# AD.net
KiCad netlist of a schematic drawn in Altium Designer
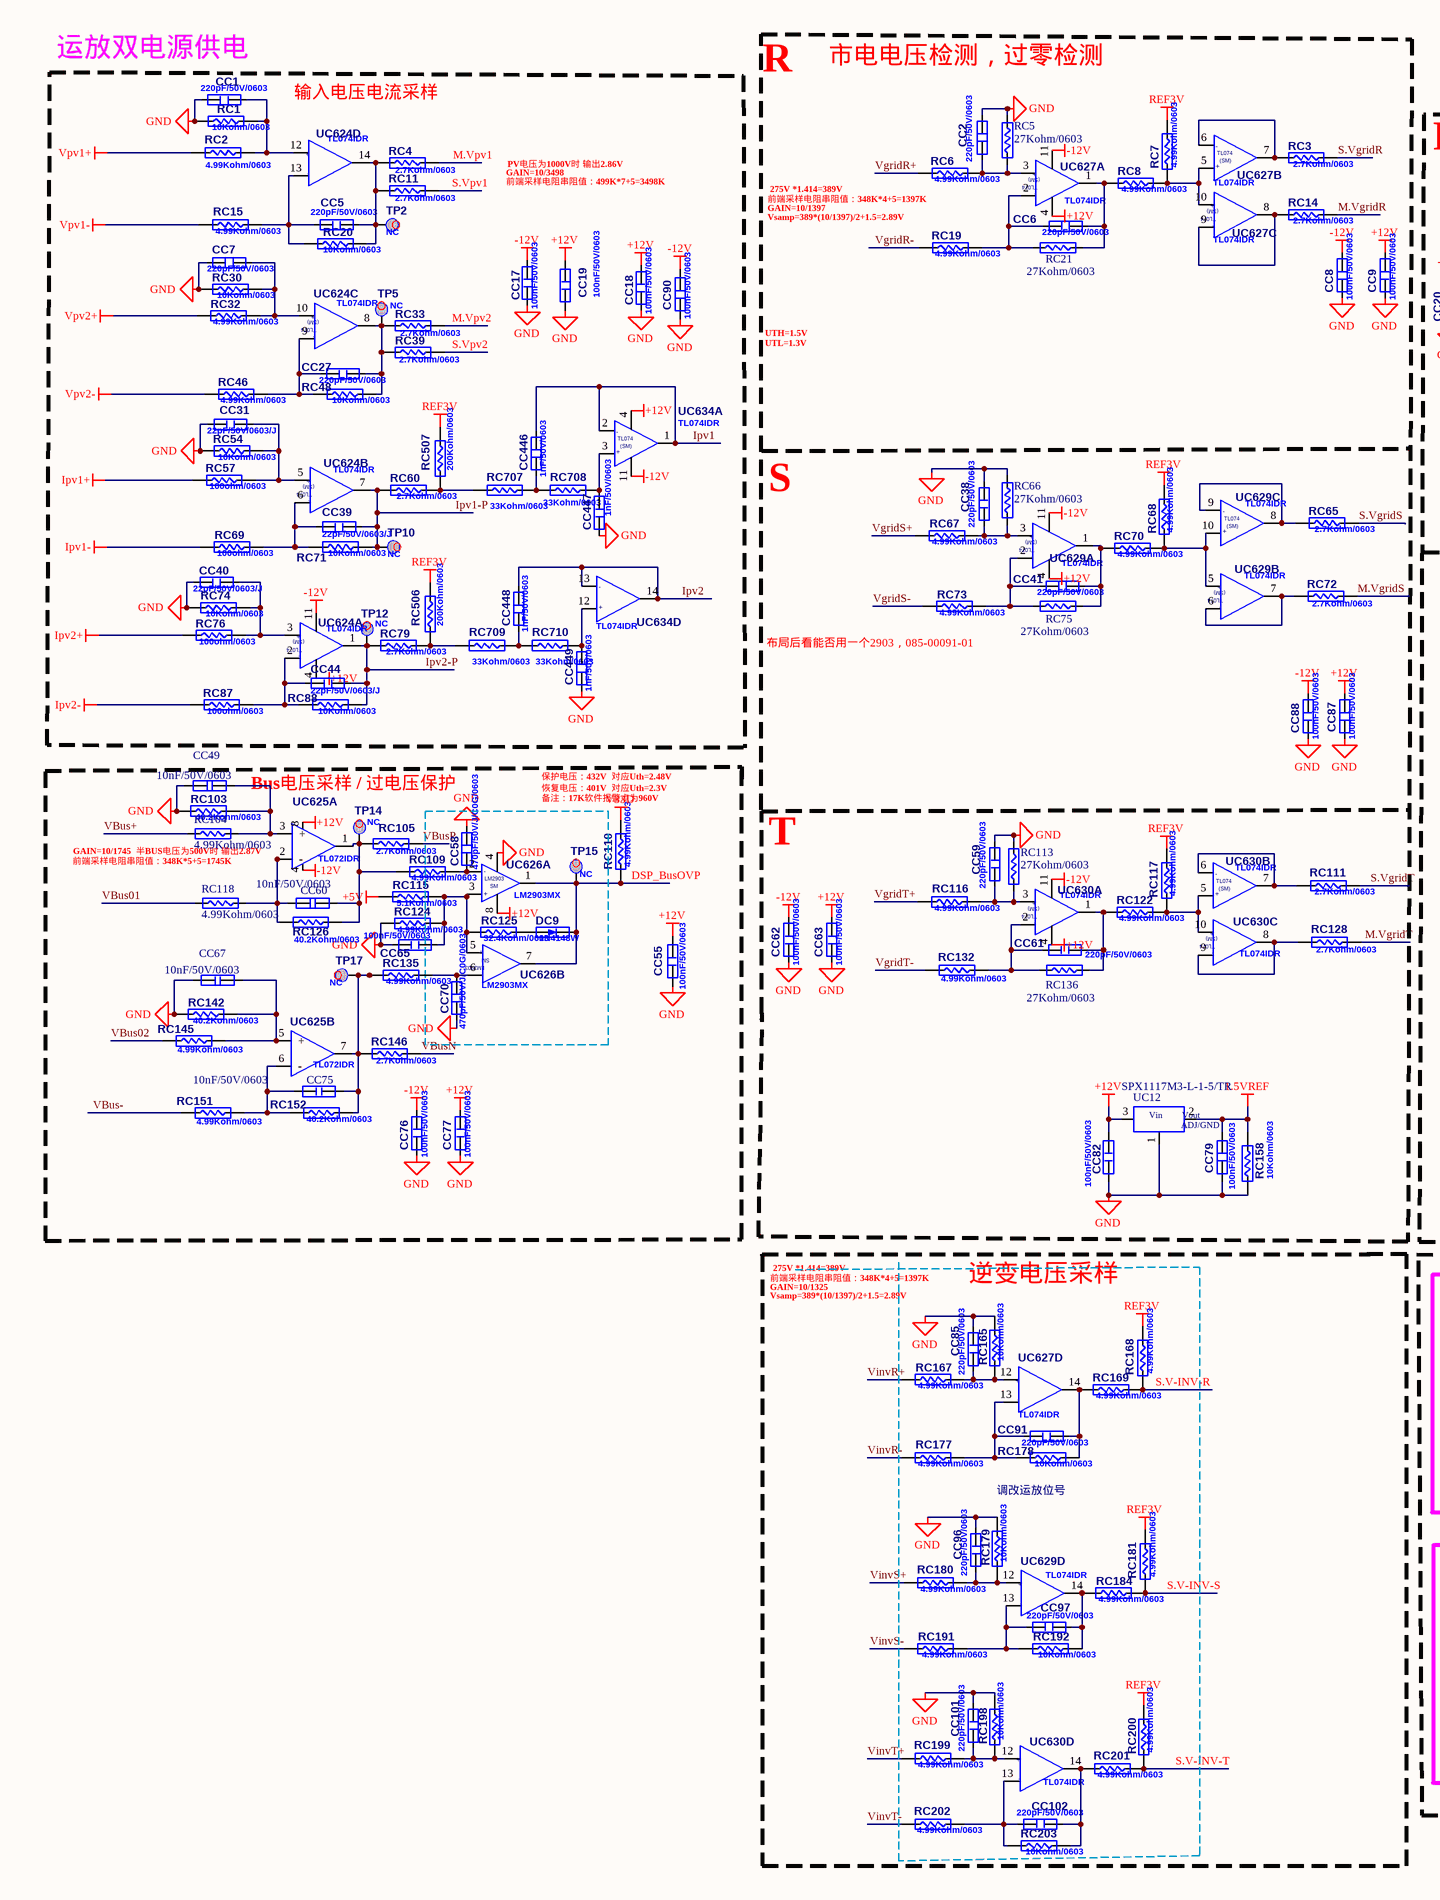
[diagram p0: AD.SchDoc, left]
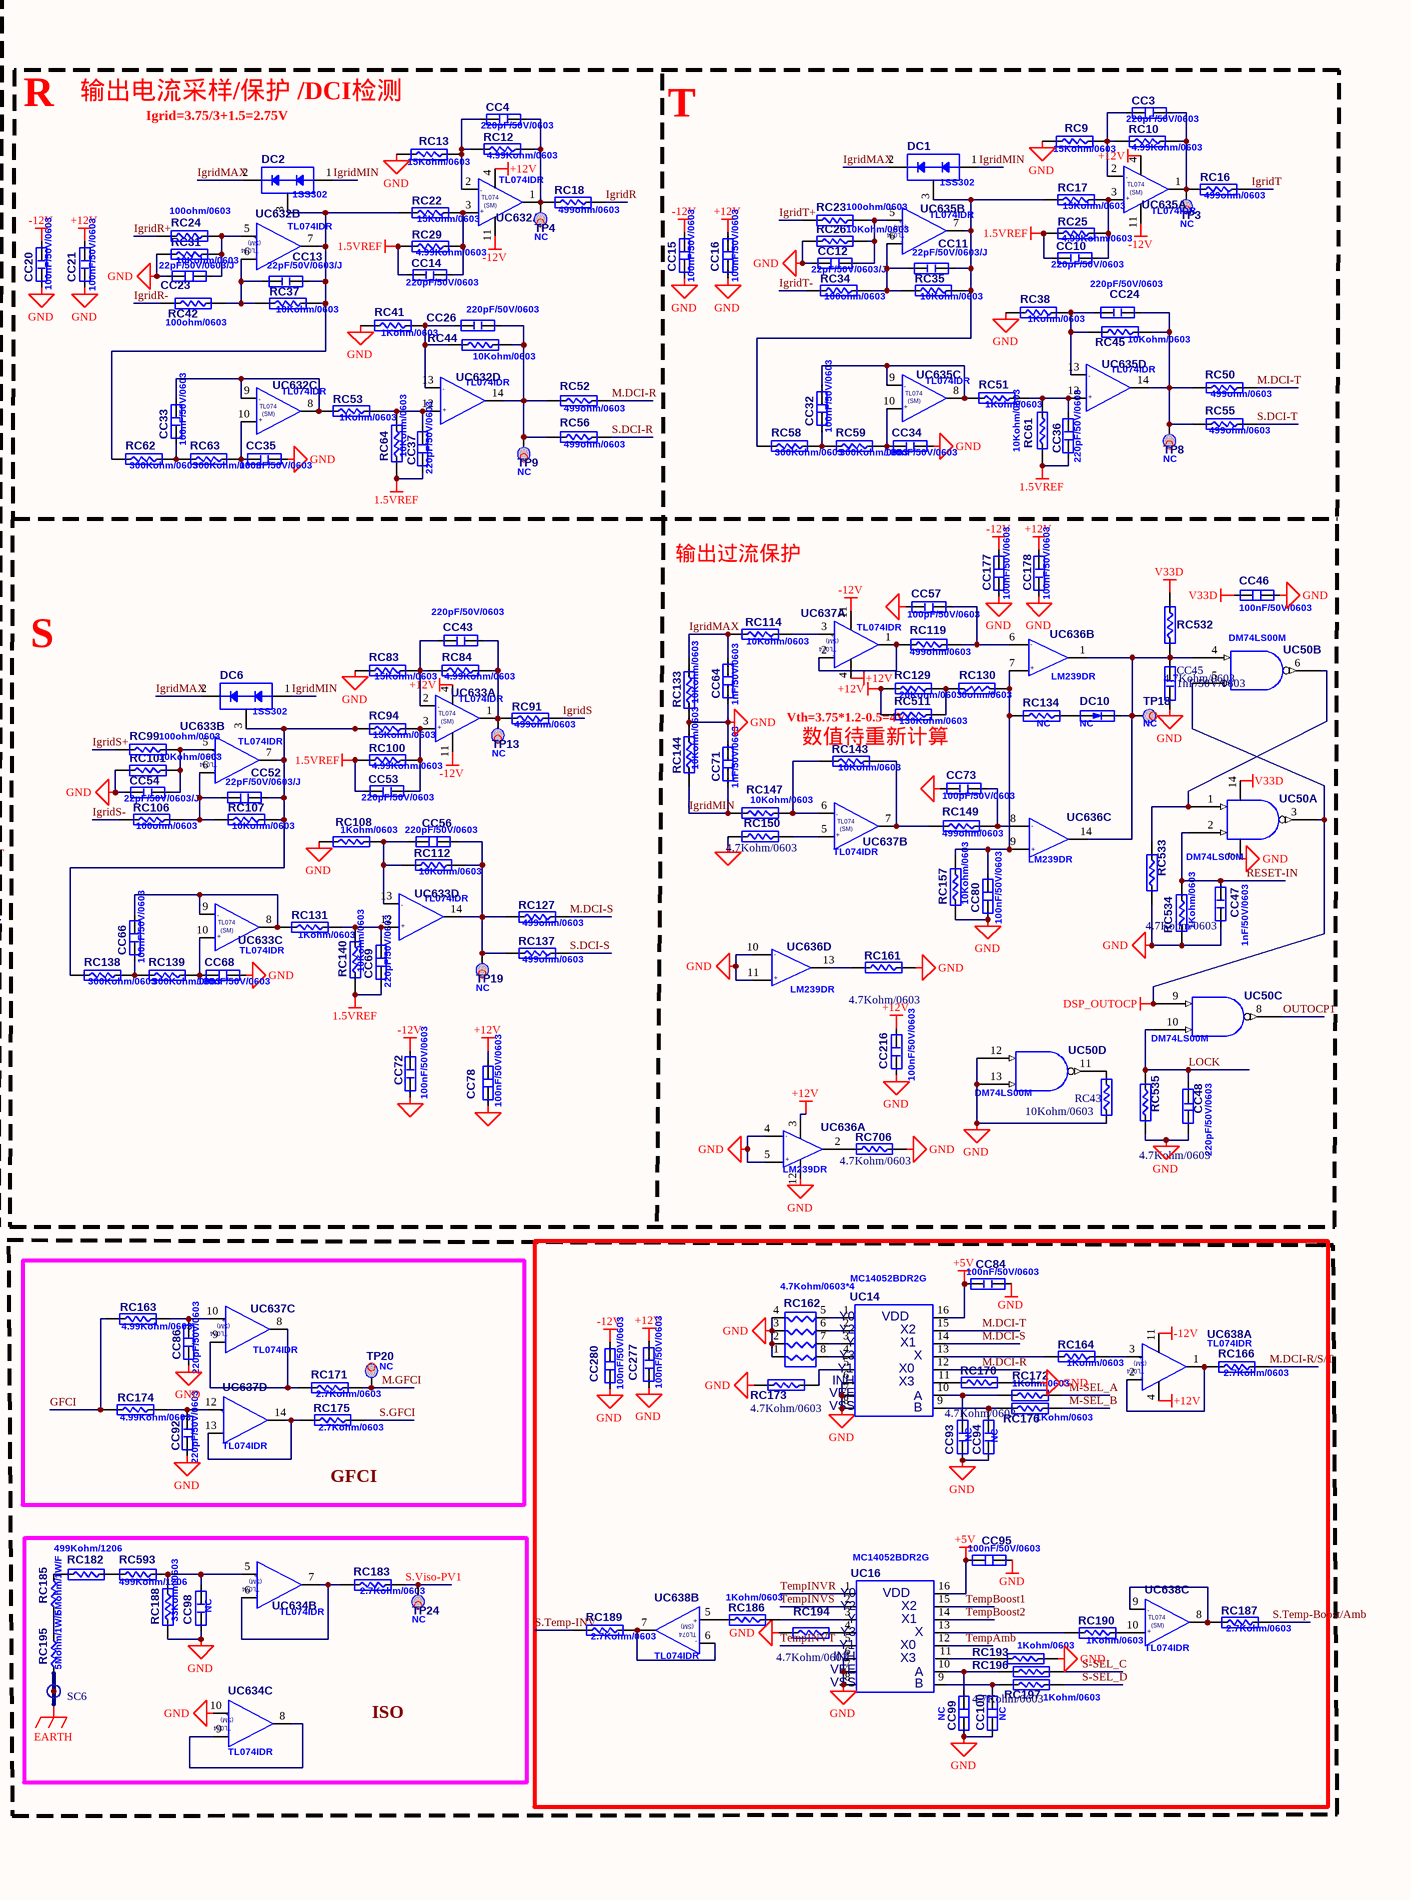
[diagram p1: AD.SchDoc, right]

(export (version "E")
  (design (tool "Eeschema 10.0.6"))
  (components
    (comp (ref "CC1")
      (value "220pF/50V/0603")
      (footprint "CC1608-0603")
      (description "220pF/50V/J/C0G/0603")
      (fields (field (name "Comment") "023-221220-0"))
      (libsource (lib "00") (part "C0603 SM"))
    )
    (comp (ref "CC2")
      (value "220pF/50V/0603")
      (footprint "CC1608-0603")
      (description "220pF/50V/J/C0G/0603")
      (fields (field (name "Comment") "023-221220-0"))
      (libsource (lib "00") (part "C0603 SM"))
    )
    (comp (ref "CC3")
      (value "220pF/50V/0603")
      (footprint "CC1608-0603")
      (description "220pF/50V/J/C0G/0603")
      (fields (field (name "Comment") "023-221220-0"))
      (libsource (lib "00") (part "C0603 SM"))
    )
    (comp (ref "CC4")
      (value "220pF/50V/0603")
      (footprint "CC1608-0603")
      (description "220pF/50V/J/C0G/0603")
      (fields (field (name "Comment") "023-221220-0"))
      (libsource (lib "00") (part "C0603 SM"))
    )
    (comp (ref "CC5")
      (value "220pF/50V/0603")
      (footprint "CC1608-0603")
      (description "220pF/50V/J/C0G/0603")
      (fields (field (name "Comment") "023-221220-0"))
      (libsource (lib "00") (part "C0603 SM"))
    )
    (comp (ref "CC6")
      (value "220pF/50V/0603")
      (footprint "CC1608-0603")
      (description "220pF/50V/J/C0G/0603")
      (fields (field (name "Comment") "023-221220-0"))
      (libsource (lib "00") (part "C0603 SM"))
    )
    (comp (ref "CC7")
      (value "220pF/50V/0603")
      (footprint "CC1608-0603")
      (description "220pF/50V/J/C0G/0603")
      (fields (field (name "Comment") "023-221220-0"))
      (libsource (lib "00") (part "C0603 SM"))
    )
    (comp (ref "CC8")
      (value "100nF/50V/0603")
      (footprint "CC1608-0603")
      (description "100nF/50V/J/X7R/0603")
      (fields (field (name "Comment") "023-105220-0"))
      (libsource (lib "00") (part "C0603 SM"))
    )
    (comp (ref "CC9")
      (value "100nF/50V/0603")
      (footprint "CC1608-0603")
      (description "100nF/50V/J/X7R/0603")
      (fields (field (name "Comment") "023-105220-0"))
      (libsource (lib "00") (part "C0603 SM"))
    )
    (comp (ref "CC10")
      (value "220pF/50V/0603")
      (footprint "CC1608-0603")
      (description "220pF/50V/J/C0G/0603")
      (fields (field (name "Comment") "023-221220-0"))
      (libsource (lib "00") (part "C0603 SM"))
    )
    (comp (ref "CC11")
      (value "22pF/50V/0603/J")
      (footprint "CC1608-0603")
      (description "22pF/50V/J/C0G/0603")
      (fields (field (name "Comment") "023-220220-0"))
      (libsource (lib "00") (part "C0603 SM"))
    )
    (comp (ref "CC12")
      (value "22pF/50V/0603/J")
      (footprint "CC1608-0603")
      (description "22pF/50V/J/C0G/0603")
      (fields (field (name "Comment") "023-220220-0"))
      (libsource (lib "00") (part "C0603 SM"))
    )
    (comp (ref "CC13")
      (value "22pF/50V/0603/J")
      (footprint "CC1608-0603")
      (description "22pF/50V/J/C0G/0603")
      (fields (field (name "Comment") "023-220220-0"))
      (libsource (lib "00") (part "C0603 SM"))
    )
    (comp (ref "CC14")
      (value "220pF/50V/0603")
      (footprint "CC1608-0603")
      (description "220pF/50V/J/C0G/0603")
      (fields (field (name "Comment") "023-221220-0"))
      (libsource (lib "00") (part "C0603 SM"))
    )
    (comp (ref "CC15")
      (value "100nF/50V/0603")
      (footprint "CC1608-0603")
      (description "100nF/50V/J/X7R/0603")
      (fields (field (name "Comment") "023-105220-0"))
      (libsource (lib "00") (part "C0603 SM"))
    )
    (comp (ref "CC16")
      (value "100nF/50V/0603")
      (footprint "CC1608-0603")
      (description "100nF/50V/J/X7R/0603")
      (fields (field (name "Comment") "023-105220-0"))
      (libsource (lib "00") (part "C0603 SM"))
    )
    (comp (ref "CC17")
      (value "100nF/50V/0603")
      (footprint "CC1608-0603")
      (description "100nF/50V/J/X7R/0603")
      (fields (field (name "Comment") "023-105220-0"))
      (libsource (lib "00") (part "C0603 SM"))
    )
    (comp (ref "CC18")
      (value "100nF/50V/0603")
      (footprint "CC1608-0603")
      (description "100nF/50V/J/X7R/0603")
      (fields (field (name "Comment") "023-105220-0"))
      (libsource (lib "00") (part "C0603 SM"))
    )
    (comp (ref "CC19")
      (value "100nF/50V/0603")
      (footprint "CC1608-0603")
      (description "100nF/50V/J/X7R/0603")
      (fields (field (name "Comment") "023-105220-0"))
      (libsource (lib "") (part "C0603 SM_1"))
    )
    (comp (ref "CC20")
      (value "100nF/50V/0603")
      (footprint "CC1608-0603")
      (description "100nF/50V/J/X7R/0603")
      (fields (field (name "Comment") "023-105220-0"))
      (libsource (lib "00") (part "C0603 SM"))
    )
    (comp (ref "CC21")
      (value "100nF/50V/0603")
      (footprint "CC1608-0603")
      (description "100nF/50V/J/X7R/0603")
      (fields (field (name "Comment") "023-105220-0"))
      (libsource (lib "00") (part "C0603 SM"))
    )
    (comp (ref "CC23")
      (value "22pF/50V/0603/J")
      (footprint "CC1608-0603")
      (description "22pF/50V/J/C0G/0603")
      (fields (field (name "Comment") "023-220220-0"))
      (libsource (lib "00") (part "C0603 SM"))
    )
    (comp (ref "CC24")
      (value "220pF/50V/0603")
      (footprint "CC1608-0603")
      (description "220pF/50V/J/C0G/0603")
      (fields (field (name "Comment") "023-221220-0"))
      (libsource (lib "00") (part "C0603 SM"))
    )
    (comp (ref "CC26")
      (value "220pF/50V/0603")
      (footprint "CC1608-0603")
      (description "220pF/50V/J/C0G/0603")
      (fields (field (name "Comment") "023-221220-0"))
      (libsource (lib "00") (part "C0603 SM"))
    )
    (comp (ref "CC27")
      (value "220pF/50V/0603")
      (footprint "CC1608-0603")
      (description "220pF/50V/J/C0G/0603")
      (fields (field (name "Comment") "023-221220-0"))
      (libsource (lib "00") (part "C0603 SM"))
    )
    (comp (ref "CC31")
      (value "22pF/50V/0603/J")
      (footprint "CC1608-0603")
      (description "22pF/50V/J/C0G/0603")
      (fields (field (name "Comment") "023-220220-0"))
      (libsource (lib "00") (part "C0603 SM"))
    )
    (comp (ref "CC32")
      (value "100nF/50V/0603")
      (footprint "CC1608-0603")
      (description "100nF/50V/J/X7R/0603")
      (fields (field (name "Comment") "023-105220-0"))
      (libsource (lib "00") (part "C0603 SM"))
    )
    (comp (ref "CC33")
      (value "100nF/50V/0603")
      (footprint "CC1608-0603")
      (description "100nF/50V/J/X7R/0603")
      (fields (field (name "Comment") "023-105220-0"))
      (libsource (lib "00") (part "C0603 SM"))
    )
    (comp (ref "CC34")
      (value "100nF/50V/0603")
      (footprint "CC1608-0603")
      (description "100nF/50V/J/X7R/0603")
      (fields (field (name "Comment") "023-105220-0"))
      (libsource (lib "00") (part "C0603 SM"))
    )
    (comp (ref "CC35")
      (value "100nF/50V/0603")
      (footprint "CC1608-0603")
      (description "100nF/50V/J/X7R/0603")
      (fields (field (name "Comment") "023-105220-0"))
      (libsource (lib "00") (part "C0603 SM"))
    )
    (comp (ref "CC36")
      (value "220pF/50V/0603")
      (footprint "CC1608-0603")
      (description "220pF/50V/J/C0G/0603")
      (fields (field (name "Comment") "023-221220-0"))
      (libsource (lib "00") (part "C0603 SM"))
    )
    (comp (ref "CC37")
      (value "220pF/50V/0603")
      (footprint "CC1608-0603")
      (description "220pF/50V/J/C0G/0603")
      (fields (field (name "Comment") "023-221220-0"))
      (libsource (lib "00") (part "C0603 SM"))
    )
    (comp (ref "CC38")
      (value "220pF/50V/0603")
      (footprint "CC1608-0603")
      (description "220pF/50V/J/C0G/0603")
      (fields (field (name "Comment") "023-221220-0"))
      (libsource (lib "00") (part "C0603 SM"))
    )
    (comp (ref "CC39")
      (value "22pF/50V/0603/J")
      (footprint "CC1608-0603")
      (description "22pF/50V/J/C0G/0603")
      (fields (field (name "Comment") "023-220220-0"))
      (libsource (lib "00") (part "C0603 SM"))
    )
    (comp (ref "CC40")
      (value "22pF/50V/0603/J")
      (footprint "CC1608-0603")
      (description "22pF/50V/J/C0G/0603")
      (fields (field (name "Comment") "023-220220-0"))
      (libsource (lib "00") (part "C0603 SM"))
    )
    (comp (ref "CC41")
      (value "220pF/50V/0603")
      (footprint "CC1608-0603")
      (description "220pF/50V/J/C0G/0603")
      (fields (field (name "Comment") "023-221220-0"))
      (libsource (lib "00") (part "C0603 SM"))
    )
    (comp (ref "CC43")
      (value "220pF/50V/0603")
      (footprint "CC1608-0603")
      (description "220pF/50V/J/C0G/0603")
      (fields (field (name "Comment") "023-221220-0"))
      (libsource (lib "00") (part "C0603 SM"))
    )
    (comp (ref "CC44")
      (value "22pF/50V/0603/J")
      (footprint "CC1608-0603")
      (description "22pF/50V/J/C0G/0603")
      (fields (field (name "Comment") "023-220220-0"))
      (libsource (lib "00") (part "C0603 SM"))
    )
    (comp (ref "CC45")
      (value "1nF/50V/0603")
      (footprint "C0603SM")
      (description "1nF/50V/J/C0G/0603")
      (fields (field (name "Comment") "023-102220-0"))
      (libsource (lib "首航") (part "023-102220-0 C0603SM"))
    )
    (comp (ref "CC46")
      (value "100nF/50V/0603")
      (footprint "CC1608-0603")
      (description "100nF/50V/J/X7R/0603")
      (fields (field (name "Comment") "023-105220-0"))
      (libsource (lib "CAP") (part "CC0603-104SM"))
    )
    (comp (ref "CC47")
      (value "1nF/50V/0603")
      (footprint "CC1608-0603")
      (description "1nF/50V/J/C0G/0603")
      (fields (field (name "Comment") "023-102220-0"))
      (libsource (lib "*") (part "C0603 SM"))
    )
    (comp (ref "CC48")
      (value "220pF/50V/0603")
      (footprint "CC1608-0603")
      (description "220pF/50V/J/C0G/0603")
      (fields (field (name "Comment") "023-221220-0"))
      (libsource (lib "*") (part "C0603SM-3"))
    )
    (comp (ref "CC49")
      (value "10nF/50V/0603")
      (footprint "C0603SM")
      (description "10nF/50V/J/X7R/0603")
      (fields (field (name "Comment") "023-103220-0"))
      (libsource (lib "首航") (part "023-103220-0 C0603SM"))
    )
    (comp (ref "CC52")
      (value "22pF/50V/0603/J")
      (footprint "CC1608-0603")
      (description "22pF/50V/J/C0G/0603")
      (fields (field (name "Comment") "023-220220-0"))
      (libsource (lib "00") (part "C0603 SM"))
    )
    (comp (ref "CC53")
      (value "220pF/50V/0603")
      (footprint "CC1608-0603")
      (description "220pF/50V/J/C0G/0603")
      (fields (field (name "Comment") "023-221220-0"))
      (libsource (lib "00") (part "C0603 SM"))
    )
    (comp (ref "CC54")
      (value "22pF/50V/0603/J")
      (footprint "CC1608-0603")
      (description "22pF/50V/J/C0G/0603")
      (fields (field (name "Comment") "023-220220-0"))
      (libsource (lib "00") (part "C0603 SM"))
    )
    (comp (ref "CC55")
      (value "100nF/50V/0603")
      (footprint "CC1608-0603")
      (description "100nF/50V/J/X7R/0603")
      (fields (field (name "Comment") "023-105220-0"))
      (libsource (lib "") (part "C0603 SM_1"))
    )
    (comp (ref "CC56")
      (value "220pF/50V/0603")
      (footprint "CC1608-0603")
      (description "220pF/50V/J/C0G/0603")
      (fields (field (name "Comment") "023-221220-0"))
      (libsource (lib "") (part "C0603 SM_1"))
    )
    (comp (ref "CC57")
      (value "100pF/50V/0603")
      (footprint "CC1608-0603")
      (description "100pF/50V/J/C0G/0603")
      (fields (field (name "Comment") "023-101220-0"))
      (libsource (lib "*") (part "C0603 SM"))
    )
    (comp (ref "CC58")
      (value "470pF/50V/J/C0G/0603")
      (footprint "CC1608-0603")
      (fields (field (name "Comment") "023-471220-0"))
      (libsource (lib "00") (part "C0603 SM"))
    )
    (comp (ref "CC59")
      (value "220pF/50V/0603")
      (footprint "CC1608-0603")
      (description "220pF/50V/J/C0G/0603")
      (fields (field (name "Comment") "023-221220-0"))
      (libsource (lib "00") (part "C0603 SM"))
    )
    (comp (ref "CC60")
      (value "10nF/50V/0603")
      (footprint "C0603SM")
      (description "10nF/50V/J/X7R/0603")
      (fields (field (name "Comment") "023-103220-0"))
      (libsource (lib "首航") (part "023-103220-0 C0603SM"))
    )
    (comp (ref "CC61")
      (value "220pF/50V/0603")
      (footprint "CC1608-0603")
      (description "220pF/50V/J/C0G/0603")
      (fields (field (name "Comment") "023-221220-0"))
      (libsource (lib "00") (part "C0603 SM"))
    )
    (comp (ref "CC62")
      (value "100nF/50V/0603")
      (footprint "CC1608-0603")
      (description "100nF/50V/J/X7R/0603")
      (fields (field (name "Comment") "023-105220-0"))
      (libsource (lib "00") (part "C0603 SM"))
    )
    (comp (ref "CC63")
      (value "100nF/50V/0603")
      (footprint "CC1608-0603")
      (description "100nF/50V/J/X7R/0603")
      (fields (field (name "Comment") "023-105220-0"))
      (libsource (lib "00") (part "C0603 SM"))
    )
    (comp (ref "CC64")
      (value "1nF/50V/0603")
      (footprint "CC1608-0603")
      (description "1nF/50V/J/C0G/0603")
      (fields (field (name "Comment") "023-102220-0"))
      (libsource (lib "*") (part "C0603 SM"))
    )
    (comp (ref "CC65")
      (value "100nF/50V/0603")
      (footprint "CC1608-0603")
      (description "100nF/50V/J/X7R/0603")
      (fields (field (name "Comment") "023-105220-0"))
      (libsource (lib "00") (part "C0603 SM"))
    )
    (comp (ref "CC66")
      (value "100nF/50V/0603")
      (footprint "CC1608-0603")
      (description "100nF/50V/J/X7R/0603")
      (fields (field (name "Comment") "023-105220-0"))
      (libsource (lib "00") (part "C0603 SM"))
    )
    (comp (ref "CC67")
      (value "10nF/50V/0603")
      (footprint "C0603SM")
      (description "10nF/50V/J/X7R/0603")
      (fields (field (name "Comment") "023-103220-0"))
      (libsource (lib "首航") (part "023-103220-0 C0603SM"))
    )
    (comp (ref "CC68")
      (value "100nF/50V/0603")
      (footprint "CC1608-0603")
      (description "100nF/50V/J/X7R/0603")
      (fields (field (name "Comment") "023-105220-0"))
      (libsource (lib "00") (part "C0603 SM"))
    )
    (comp (ref "CC69")
      (value "220pF/50V/0603")
      (footprint "CC1608-0603")
      (description "220pF/50V/J/C0G/0603")
      (fields (field (name "Comment") "023-221220-0"))
      (libsource (lib "") (part "C0603 SM_1"))
    )
    (comp (ref "CC70")
      (value "470pF/50V/J/C0G/0603")
      (footprint "CC1608-0603")
      (fields (field (name "Comment") "023-471220-0"))
      (libsource (lib "00") (part "C0603 SM"))
    )
    (comp (ref "CC71")
      (value "1nF/50V/0603")
      (footprint "CC1608-0603")
      (description "1nF/50V/J/C0G/0603")
      (fields (field (name "Comment") "023-102220-0"))
      (libsource (lib "*") (part "C0603 SM"))
    )
    (comp (ref "CC72")
      (value "100nF/50V/0603")
      (footprint "CC1608-0603")
      (description "100nF/50V/J/X7R/0603")
      (fields (field (name "Comment") "023-105220-0"))
      (libsource (lib "*") (part "C0603 SM"))
    )
    (comp (ref "CC73")
      (value "100pF/50V/0603")
      (footprint "CC1608-0603")
      (description "100pF/50V/J/C0G/0603")
      (fields (field (name "Comment") "023-101220-0"))
      (libsource (lib "*") (part "C0603 SM"))
    )
    (comp (ref "CC75")
      (value "10nF/50V/0603")
      (footprint "C0603SM")
      (description "10nF/50V/J/X7R/0603")
      (fields (field (name "Comment") "023-103220-0"))
      (libsource (lib "首航") (part "023-103220-0 C0603SM"))
    )
    (comp (ref "CC76")
      (value "100nF/50V/0603")
      (footprint "CC1608-0603")
      (description "100nF/50V/J/X7R/0603")
      (fields (field (name "Comment") "023-105220-0"))
      (libsource (lib "00") (part "C0603 SM"))
    )
    (comp (ref "CC77")
      (value "100nF/50V/0603")
      (footprint "CC1608-0603")
      (description "100nF/50V/J/X7R/0603")
      (fields (field (name "Comment") "023-105220-0"))
      (libsource (lib "00") (part "C0603 SM"))
    )
    (comp (ref "CC78")
      (value "100nF/50V/0603")
      (footprint "CC1608-0603")
      (description "100nF/50V/J/X7R/0603")
      (fields (field (name "Comment") "023-105220-0"))
      (libsource (lib "*") (part "C0603 SM"))
    )
    (comp (ref "CC79")
      (value "100nF/50V/0603")
      (footprint "CC1608-0603")
      (description "100nF/50V/J/X7R/0603")
      (fields (field (name "Comment") "023-105220-0"))
      (libsource (lib "") (part "C0603 SM_1"))
    )
    (comp (ref "CC80")
      (value "100nF/50V/0603")
      (footprint "CC1608-0603")
      (description "100nF/50V/J/X7R/0603")
      (fields (field (name "Comment") "023-105220-0"))
      (libsource (lib "00") (part "C0603 SM"))
    )
    (comp (ref "CC82")
      (value "100nF/50V/0603")
      (footprint "CC1608-0603")
      (description "100nF/50V/J/X7R/0603")
      (fields (field (name "Comment") "023-105220-0"))
      (libsource (lib "") (part "C0603 SM_1"))
    )
    (comp (ref "CC84")
      (value "100nF/50V/0603")
      (footprint "CC1608-0603")
      (description "100nF/50V/J/X7R/0603")
      (fields (field (name "Comment") "023-105220-0"))
      (libsource (lib "00") (part "C0603 SM"))
    )
    (comp (ref "CC85")
      (value "220pF/50V/0603")
      (footprint "CC1608-0603")
      (description "220pF/50V/J/C0G/0603")
      (fields (field (name "Comment") "023-221220-0"))
      (libsource (lib "00") (part "C0603 SM"))
    )
    (comp (ref "CC86")
      (value "220pF/50V/0603")
      (footprint "CC1608-0603")
      (description "220pF/50V/J/C0G/0603")
      (fields (field (name "Comment") "023-221220-0"))
      (libsource (lib "00") (part "C0603 SM"))
    )
    (comp (ref "CC87")
      (value "100nF/50V/0603")
      (footprint "CC1608-0603")
      (description "100nF/50V/J/X7R/0603")
      (fields (field (name "Comment") "023-105220-0"))
      (libsource (lib "00") (part "C0603 SM"))
    )
    (comp (ref "CC88")
      (value "100nF/50V/0603")
      (footprint "CC1608-0603")
      (description "100nF/50V/J/X7R/0603")
      (fields (field (name "Comment") "023-105220-0"))
      (libsource (lib "00") (part "C0603 SM"))
    )
    (comp (ref "CC90")
      (value "100nF/50V/0603")
      (footprint "CC1608-0603")
      (description "100nF/50V/J/X7R/0603")
      (fields (field (name "Comment") "023-105220-0"))
      (libsource (lib "") (part "C0603 SM_1"))
    )
    (comp (ref "CC91")
      (value "220pF/50V/0603")
      (footprint "CC1608-0603")
      (description "220pF/50V/J/C0G/0603")
      (fields (field (name "Comment") "023-221220-0"))
      (libsource (lib "00") (part "C0603 SM"))
    )
    (comp (ref "CC92")
      (value "220pF/50V/0603")
      (footprint "CC1608-0603")
      (description "220pF/50V/J/C0G/0603")
      (fields (field (name "Comment") "023-221220-0"))
      (libsource (lib "00") (part "C0603 SM"))
    )
    (comp (ref "CC93") (value "NC") (footprint "CC1608-0603") (libsource (lib "00") (part "C0603 SM")))
    (comp (ref "CC94") (value "NC") (footprint "CC1608-0603") (libsource (lib "00") (part "C0603 SM")))
    (comp (ref "CC95")
      (value "100nF/50V/0603")
      (footprint "CC1608-0603")
      (description "100nF/50V/J/X7R/0603")
      (fields (field (name "Comment") "023-105220-0"))
      (libsource (lib "00") (part "C0603 SM"))
    )
    (comp (ref "CC96")
      (value "220pF/50V/0603")
      (footprint "CC1608-0603")
      (description "220pF/50V/J/C0G/0603")
      (fields (field (name "Comment") "023-221220-0"))
      (libsource (lib "00") (part "C0603 SM"))
    )
    (comp (ref "CC97")
      (value "220pF/50V/0603")
      (footprint "CC1608-0603")
      (description "220pF/50V/J/C0G/0603")
      (fields (field (name "Comment") "023-221220-0"))
      (libsource (lib "00") (part "C0603 SM"))
    )
    (comp (ref "CC98") (value "NC") (footprint "CC1608-0603") (libsource (lib "00") (part "C0603 SM")))
    (comp (ref "CC99") (value "NC") (footprint "CC1608-0603") (libsource (lib "00") (part "C0603 SM")))
    (comp (ref "CC100") (value "NC") (footprint "CC1608-0603") (libsource (lib "00") (part "C0603 SM")))
    (comp (ref "CC101")
      (value "220pF/50V/0603")
      (footprint "CC1608-0603")
      (description "220pF/50V/J/C0G/0603")
      (fields (field (name "Comment") "023-221220-0"))
      (libsource (lib "00") (part "C0603 SM"))
    )
    (comp (ref "CC102")
      (value "220pF/50V/0603")
      (footprint "CC1608-0603")
      (description "220pF/50V/J/C0G/0603")
      (fields (field (name "Comment") "023-221220-0"))
      (libsource (lib "00") (part "C0603 SM"))
    )
    (comp (ref "CC177")
      (value "100nF/50V/0603")
      (footprint "CC1608-0603")
      (description "100nF/50V/J/X7R/0603")
      (fields (field (name "Comment") "023-105220-0"))
      (libsource (lib "00") (part "C0603 SM"))
    )
    (comp (ref "CC178")
      (value "100nF/50V/0603")
      (footprint "CC1608-0603")
      (description "100nF/50V/J/X7R/0603")
      (fields (field (name "Comment") "023-105220-0"))
      (libsource (lib "00") (part "C0603 SM"))
    )
    (comp (ref "CC216")
      (value "100nF/50V/0603")
      (footprint "CC1608-0603")
      (description "100nF/50V/J/X7R/0603")
      (fields (field (name "Comment") "023-105220-0"))
      (libsource (lib "00") (part "C0603 SM"))
    )
    (comp (ref "CC277")
      (value "100nF/50V/0603")
      (footprint "CC1608-0603")
      (description "100nF/50V/J/X7R/0603")
      (fields (field (name "Comment") "023-105220-0"))
      (libsource (lib "00") (part "C0603 SM"))
    )
    (comp (ref "CC280")
      (value "100nF/50V/0603")
      (footprint "CC1608-0603")
      (description "100nF/50V/J/X7R/0603")
      (fields (field (name "Comment") "023-105220-0"))
      (libsource (lib "00") (part "C0603 SM"))
    )
    (comp (ref "CC446")
      (value "1nF/50V/0603")
      (footprint "CC1608-0603")
      (description "1nF/50V/J/C0G/0603")
      (fields (field (name "Comment") "023-102220-0"))
      (libsource (lib "00") (part "C0603 SM"))
    )
    (comp (ref "CC447")
      (value "1nF/50V/0603")
      (footprint "CC1608-0603")
      (description "1nF/50V/J/C0G/0603")
      (fields (field (name "Comment") "023-102220-0"))
      (libsource (lib "00") (part "C0603 SM"))
    )
    (comp (ref "CC448")
      (value "1nF/50V/0603")
      (footprint "CC1608-0603")
      (description "1nF/50V/J/C0G/0603")
      (fields (field (name "Comment") "023-102220-0"))
      (libsource (lib "00") (part "C0603 SM"))
    )
    (comp (ref "CC449")
      (value "1nF/50V/0603")
      (footprint "CC1608-0603")
      (description "1nF/50V/J/C0G/0603")
      (fields (field (name "Comment") "023-102220-0"))
      (libsource (lib "00") (part "C0603 SM"))
    )
    (comp (ref "DC1")
      (value "1SS302")
      (footprint "SC-70")
      (description "0.1A/80V/SC-70")
      (fields (field (name "Comment") "060-610010-0"))
      (libsource (lib "00") (part "17K1SS302"))
    )
    (comp (ref "DC2")
      (value "1SS302")
      (footprint "SC-70")
      (description "0.1A/80V/SC-70")
      (fields (field (name "Comment") "060-610010-0"))
      (libsource (lib "00") (part "17K1SS302"))
    )
    (comp (ref "DC6")
      (value "1SS302")
      (footprint "SC-70")
      (description "0.1A/80V/SC-70")
      (fields (field (name "Comment") "060-610010-0"))
      (libsource (lib "00") (part "17K1SS302"))
    )
    (comp (ref "DC9")
      (value "1N4148W")
      (footprint "SOD-123")
      (description "0.15A/75V/SOD-123")
      (fields (field (name "Comment") "060-500010-0"))
      (libsource (lib "00") (part "D 1N4148W"))
    )
    (comp (ref "DC10") (value "NC") (footprint "SOD-123") (libsource (lib "00") (part "D 1N4148W")))
    (comp (ref "RC1")
      (value "10Kohm/0603")
      (footprint "R1608-0603")
      (description "10Kohm/1/10W/F/0603")
      (fields (field (name "Comment") "011-103020-0"))
      (libsource (lib "00") (part "R0603SM"))
    )
    (comp (ref "RC2")
      (value "4.99Kohm/0603")
      (footprint "R1608-0603")
      (description "4.99Kohm/1/10W/F/0603")
      (fields (field (name "Comment") "011-492020-0"))
      (libsource (lib "00") (part "R0603SM"))
    )
    (comp (ref "RC3")
      (value "2.7Kohm/0603")
      (footprint "R1608-0603")
      (description "2.7Kohm/1/10W/F/0603")
      (fields (field (name "Comment") "011-272020-0"))
      (libsource (lib "00") (part "R0603SM"))
    )
    (comp (ref "RC4")
      (value "2.7Kohm/0603")
      (footprint "R1608-0603")
      (description "2.7Kohm/1/10W/F/0603")
      (fields (field (name "Comment") "011-272020-0"))
      (libsource (lib "00") (part "R0603SM"))
    )
    (comp (ref "RC5")
      (value "27Kohm/0603")
      (footprint "R0603SM")
      (description "27Kohm/1/10W/F/0603")
      (fields (field (name "Comment") "011-273020-0"))
      (libsource (lib "首航") (part "011-273020-0 R0603SM"))
    )
    (comp (ref "RC6")
      (value "4.99Kohm/0603")
      (footprint "R1608-0603")
      (description "4.99Kohm/1/10W/F/0603")
      (fields (field (name "Comment") "011-492020-0"))
      (libsource (lib "00") (part "R0603SM"))
    )
    (comp (ref "RC7")
      (value "4.99Kohm/0603")
      (footprint "R1608-0603")
      (description "4.99Kohm/1/10W/F/0603")
      (fields (field (name "Comment") "011-492020-0"))
      (libsource (lib "00") (part "R0603SM"))
    )
    (comp (ref "RC8")
      (value "4.99Kohm/0603")
      (footprint "R1608-0603")
      (description "4.99Kohm/1/10W/F/0603")
      (fields (field (name "Comment") "011-492020-0"))
      (libsource (lib "00") (part "R0603SM"))
    )
    (comp (ref "RC9")
      (value "15Kohm/0603")
      (footprint "R1608-0603")
      (description "15Kohm/1/10W/F/0603")
      (fields (field (name "Comment") "011-153020-0"))
      (libsource (lib "00") (part "R0603SM"))
    )
    (comp (ref "RC10")
      (value "4.99Kohm/0603")
      (footprint "R1608-0603")
      (description "4.99Kohm/1/10W/F/0603")
      (fields (field (name "Comment") "011-492020-0"))
      (libsource (lib "00") (part "R0603SM"))
    )
    (comp (ref "RC11")
      (value "2.7Kohm/0603")
      (footprint "R1608-0603")
      (description "2.7Kohm/1/10W/F/0603")
      (fields (field (name "Comment") "011-272020-0"))
      (libsource (lib "00") (part "R0603SM"))
    )
    (comp (ref "RC12")
      (value "4.99Kohm/0603")
      (footprint "R1608-0603")
      (description "4.99Kohm/1/10W/F/0603")
      (fields (field (name "Comment") "011-492020-0"))
      (libsource (lib "00") (part "R0603SM"))
    )
    (comp (ref "RC13")
      (value "15Kohm/0603")
      (footprint "R1608-0603")
      (description "15Kohm/1/10W/F/0603")
      (fields (field (name "Comment") "011-153020-0"))
      (libsource (lib "00") (part "R0603SM"))
    )
    (comp (ref "RC14")
      (value "2.7Kohm/0603")
      (footprint "R1608-0603")
      (description "2.7Kohm/1/10W/F/0603")
      (fields (field (name "Comment") "011-272020-0"))
      (libsource (lib "00") (part "R0603SM"))
    )
    (comp (ref "RC15")
      (value "4.99Kohm/0603")
      (footprint "R1608-0603")
      (description "4.99Kohm/1/10W/F/0603")
      (fields (field (name "Comment") "011-492020-0"))
      (libsource (lib "00") (part "R0603SM"))
    )
    (comp (ref "RC16")
      (value "499ohm/0603")
      (footprint "R1608-0603")
      (description "499ohm/1/10W/F/0603")
      (fields (field (name "Comment") "011-491020-0"))
      (libsource (lib "00") (part "R0603SM"))
    )
    (comp (ref "RC17")
      (value "15Kohm/0603")
      (footprint "R1608-0603")
      (description "15Kohm/1/10W/F/0603")
      (fields (field (name "Comment") "011-153020-0"))
      (libsource (lib "00") (part "R0603SM"))
    )
    (comp (ref "RC18")
      (value "499ohm/0603")
      (footprint "R1608-0603")
      (description "499ohm/1/10W/F/0603")
      (fields (field (name "Comment") "011-491020-0"))
      (libsource (lib "00") (part "R0603SM"))
    )
    (comp (ref "RC19")
      (value "4.99Kohm/0603")
      (footprint "R1608-0603")
      (description "4.99Kohm/1/10W/F/0603")
      (fields (field (name "Comment") "011-492020-0"))
      (libsource (lib "00") (part "R0603SM"))
    )
    (comp (ref "RC20")
      (value "10Kohm/0603")
      (footprint "R1608-0603")
      (description "10Kohm/1/10W/F/0603")
      (fields (field (name "Comment") "011-103020-0"))
      (libsource (lib "00") (part "R0603SM"))
    )
    (comp (ref "RC21")
      (value "27Kohm/0603")
      (footprint "R0603SM")
      (description "27Kohm/1/10W/F/0603")
      (fields (field (name "Comment") "011-273020-0"))
      (libsource (lib "首航") (part "011-273020-0 R0603SM"))
    )
    (comp (ref "RC22")
      (value "15Kohm/0603")
      (footprint "R1608-0603")
      (description "15Kohm/1/10W/F/0603")
      (fields (field (name "Comment") "011-153020-0"))
      (libsource (lib "00") (part "R0603SM"))
    )
    (comp (ref "RC23")
      (value "100ohm/0603")
      (footprint "R1608-0603")
      (description "100ohm/1/10W/F/0603")
      (fields (field (name "Comment") "011-101020-0"))
      (libsource (lib "00") (part "R0603SM"))
    )
    (comp (ref "RC24")
      (value "100ohm/0603")
      (footprint "R1608-0603")
      (description "100ohm/1/10W/F/0603")
      (fields (field (name "Comment") "011-101020-0"))
      (libsource (lib "00") (part "R0603SM"))
    )
    (comp (ref "RC25")
      (value "4.99Kohm/0603")
      (footprint "R1608-0603")
      (description "4.99Kohm/1/10W/F/0603")
      (fields (field (name "Comment") "011-492020-0"))
      (libsource (lib "00") (part "R0603SM"))
    )
    (comp (ref "RC26")
      (value "10Kohm/0603")
      (footprint "R1608-0603")
      (description "10Kohm/1/10W/F/0603")
      (fields (field (name "Comment") "011-103020-0"))
      (libsource (lib "00") (part "R0603SM"))
    )
    (comp (ref "RC29")
      (value "4.99Kohm/0603")
      (footprint "R1608-0603")
      (description "4.99Kohm/1/10W/F/0603")
      (fields (field (name "Comment") "011-492020-0"))
      (libsource (lib "00") (part "R0603SM"))
    )
    (comp (ref "RC30")
      (value "10Kohm/0603")
      (footprint "R1608-0603")
      (description "10Kohm/1/10W/F/0603")
      (fields (field (name "Comment") "011-103020-0"))
      (libsource (lib "00") (part "R0603SM"))
    )
    (comp (ref "RC31")
      (value "10Kohm/0603")
      (footprint "R1608-0603")
      (description "10Kohm/1/10W/F/0603")
      (fields (field (name "Comment") "011-103020-0"))
      (libsource (lib "00") (part "R0603SM"))
    )
    (comp (ref "RC32")
      (value "4.99Kohm/0603")
      (footprint "R1608-0603")
      (description "4.99Kohm/1/10W/F/0603")
      (fields (field (name "Comment") "011-492020-0"))
      (libsource (lib "00") (part "R0603SM"))
    )
    (comp (ref "RC33")
      (value "2.7Kohm/0603")
      (footprint "R1608-0603")
      (description "2.7Kohm/1/10W/F/0603")
      (fields (field (name "Comment") "011-272020-0"))
      (libsource (lib "00") (part "R0603SM"))
    )
    (comp (ref "RC34")
      (value "100ohm/0603")
      (footprint "R1608-0603")
      (description "100ohm/1/10W/F/0603")
      (fields (field (name "Comment") "011-101020-0"))
      (libsource (lib "00") (part "R0603SM"))
    )
    (comp (ref "RC35")
      (value "10Kohm/0603")
      (footprint "R1608-0603")
      (description "10Kohm/1/10W/F/0603")
      (fields (field (name "Comment") "011-103020-0"))
      (libsource (lib "00") (part "R0603SM"))
    )
    (comp (ref "RC37")
      (value "10Kohm/0603")
      (footprint "R1608-0603")
      (description "10Kohm/1/10W/F/0603")
      (fields (field (name "Comment") "011-103020-0"))
      (libsource (lib "00") (part "R0603SM"))
    )
    (comp (ref "RC38")
      (value "1Kohm/0603")
      (footprint "R1608-0603")
      (description "1Kohm/1/10W/F/0603")
      (fields (field (name "Comment") "011-102020-0"))
      (libsource (lib "00") (part "R0603SM"))
    )
    (comp (ref "RC39")
      (value "2.7Kohm/0603")
      (footprint "R1608-0603")
      (description "2.7Kohm/1/10W/F/0603")
      (fields (field (name "Comment") "011-272020-0"))
      (libsource (lib "00") (part "R0603SM"))
    )
    (comp (ref "RC41")
      (value "1Kohm/0603")
      (footprint "R1608-0603")
      (description "1Kohm/1/10W/F/0603")
      (fields (field (name "Comment") "011-102020-0"))
      (libsource (lib "00") (part "R0603SM"))
    )
    (comp (ref "RC42")
      (value "100ohm/0603")
      (footprint "R1608-0603")
      (description "100ohm/1/10W/F/0603")
      (fields (field (name "Comment") "011-101020-0"))
      (libsource (lib "00") (part "R0603SM"))
    )
    (comp (ref "RC43")
      (value "10Kohm/0603")
      (footprint "R0603SM")
      (description "10Kohm/1/10W/F/0603")
      (fields (field (name "Comment") "011-103020-0"))
      (libsource (lib "首航") (part "011-103020-0 R0603SM"))
    )
    (comp (ref "RC44")
      (value "10Kohm/0603")
      (footprint "R1608-0603")
      (description "10Kohm/1/10W/F/0603")
      (fields (field (name "Comment") "011-103020-0"))
      (libsource (lib "00") (part "R0603SM"))
    )
    (comp (ref "RC45")
      (value "10Kohm/0603")
      (footprint "R1608-0603")
      (description "10Kohm/1/10W/F/0603")
      (fields (field (name "Comment") "011-103020-0"))
      (libsource (lib "00") (part "R0603SM"))
    )
    (comp (ref "RC46")
      (value "4.99Kohm/0603")
      (footprint "R1608-0603")
      (description "4.99Kohm/1/10W/F/0603")
      (fields (field (name "Comment") "011-492020-0"))
      (libsource (lib "00") (part "R0603SM"))
    )
    (comp (ref "RC48")
      (value "10Kohm/0603")
      (footprint "R1608-0603")
      (description "10Kohm/1/10W/F/0603")
      (fields (field (name "Comment") "011-103020-0"))
      (libsource (lib "00") (part "R0603SM"))
    )
    (comp (ref "RC50")
      (value "499ohm/0603")
      (footprint "R1608-0603")
      (description "499ohm/1/10W/F/0603")
      (fields (field (name "Comment") "011-491020-0"))
      (libsource (lib "00") (part "R0603SM"))
    )
    (comp (ref "RC51")
      (value "1Kohm/0603")
      (footprint "R1608-0603")
      (description "1Kohm/1/10W/F/0603")
      (fields (field (name "Comment") "011-102020-0"))
      (libsource (lib "00") (part "R0603SM"))
    )
    (comp (ref "RC52")
      (value "499ohm/0603")
      (footprint "R1608-0603")
      (description "499ohm/1/10W/F/0603")
      (fields (field (name "Comment") "011-491020-0"))
      (libsource (lib "00") (part "R0603SM"))
    )
    (comp (ref "RC53")
      (value "1Kohm/0603")
      (footprint "R1608-0603")
      (description "1Kohm/1/10W/F/0603")
      (fields (field (name "Comment") "011-102020-0"))
      (libsource (lib "00") (part "R0603SM"))
    )
    (comp (ref "RC54")
      (value "10Kohm/0603")
      (footprint "R1608-0603")
      (description "10Kohm/1/10W/F/0603")
      (fields (field (name "Comment") "011-103020-0"))
      (libsource (lib "00") (part "R0603SM"))
    )
    (comp (ref "RC55")
      (value "499ohm/0603")
      (footprint "R1608-0603")
      (description "499ohm/1/10W/F/0603")
      (fields (field (name "Comment") "011-491020-0"))
      (libsource (lib "00") (part "R0603SM"))
    )
    (comp (ref "RC56")
      (value "499ohm/0603")
      (footprint "R1608-0603")
      (description "499ohm/1/10W/F/0603")
      (fields (field (name "Comment") "011-491020-0"))
      (libsource (lib "00") (part "R0603SM"))
    )
    (comp (ref "RC57")
      (value "100ohm/0603")
      (footprint "R1608-0603")
      (description "100ohm/1/10W/F/0603")
      (fields (field (name "Comment") "011-101020-0"))
      (libsource (lib "00") (part "R0603SM"))
    )
    (comp (ref "RC58")
      (value "300Kohm/0603")
      (footprint "R1608-0603")
      (description "300Kohm/1/10W/F/0603")
      (fields (field (name "Comment") "011-304021-0"))
      (libsource (lib "00") (part "R0603SM"))
    )
    (comp (ref "RC59")
      (value "300Kohm/0603")
      (footprint "R1608-0603")
      (description "300Kohm/1/10W/F/0603")
      (fields (field (name "Comment") "011-304021-0"))
      (libsource (lib "00") (part "R0603SM"))
    )
    (comp (ref "RC60")
      (value "2.7Kohm/0603")
      (footprint "R1608-0603")
      (description "2.7Kohm/1/10W/F/0603")
      (fields (field (name "Comment") "011-272020-0"))
      (libsource (lib "00") (part "R0603SM"))
    )
    (comp (ref "RC61")
      (value "10Kohm/0603")
      (footprint "R1608-0603")
      (description "10Kohm/1/10W/F/0603")
      (fields (field (name "Comment") "011-103020-0"))
      (libsource (lib "00") (part "R0603SM"))
    )
    (comp (ref "RC62")
      (value "300Kohm/0603")
      (footprint "R1608-0603")
      (description "300Kohm/1/10W/F/0603")
      (fields (field (name "Comment") "011-304021-0"))
      (libsource (lib "00") (part "R0603SM"))
    )
    (comp (ref "RC63")
      (value "300Kohm/0603")
      (footprint "R1608-0603")
      (description "300Kohm/1/10W/F/0603")
      (fields (field (name "Comment") "011-304021-0"))
      (libsource (lib "00") (part "R0603SM"))
    )
    (comp (ref "RC64")
      (value "10Kohm/0603")
      (footprint "R1608-0603")
      (description "10Kohm/1/10W/F/0603")
      (fields (field (name "Comment") "011-103020-0"))
      (libsource (lib "00") (part "R0603SM"))
    )
    (comp (ref "RC65")
      (value "2.7Kohm/0603")
      (footprint "R1608-0603")
      (description "2.7Kohm/1/10W/F/0603")
      (fields (field (name "Comment") "011-272020-0"))
      (libsource (lib "00") (part "R0603SM"))
    )
    (comp (ref "RC66")
      (value "27Kohm/0603")
      (footprint "R0603SM")
      (description "27Kohm/1/10W/F/0603")
      (fields (field (name "Comment") "011-273020-0"))
      (libsource (lib "首航") (part "011-273020-0 R0603SM"))
    )
    (comp (ref "RC67")
      (value "4.99Kohm/0603")
      (footprint "R1608-0603")
      (description "4.99Kohm/1/10W/F/0603")
      (fields (field (name "Comment") "011-492020-0"))
      (libsource (lib "00") (part "R0603SM"))
    )
    (comp (ref "RC68")
      (value "4.99Kohm/0603")
      (footprint "R1608-0603")
      (description "4.99Kohm/1/10W/F/0603")
      (fields (field (name "Comment") "011-492020-0"))
      (libsource (lib "00") (part "R0603SM"))
    )
    (comp (ref "RC69")
      (value "100ohm/0603")
      (footprint "R1608-0603")
      (description "100ohm/1/10W/F/0603")
      (fields (field (name "Comment") "011-101020-0"))
      (libsource (lib "00") (part "R0603SM"))
    )
    (comp (ref "RC70")
      (value "4.99Kohm/0603")
      (footprint "R1608-0603")
      (description "4.99Kohm/1/10W/F/0603")
      (fields (field (name "Comment") "011-492020-0"))
      (libsource (lib "00") (part "R0603SM"))
    )
    (comp (ref "RC71")
      (value "10Kohm/0603")
      (footprint "R1608-0603")
      (description "10Kohm/1/10W/F/0603")
      (fields (field (name "Comment") "011-103020-0"))
      (libsource (lib "00") (part "R0603SM"))
    )
    (comp (ref "RC72")
      (value "2.7Kohm/0603")
      (footprint "R1608-0603")
      (description "2.7Kohm/1/10W/F/0603")
      (fields (field (name "Comment") "011-272020-0"))
      (libsource (lib "00") (part "R0603SM"))
    )
    (comp (ref "RC73")
      (value "4.99Kohm/0603")
      (footprint "R1608-0603")
      (description "4.99Kohm/1/10W/F/0603")
      (fields (field (name "Comment") "011-492020-0"))
      (libsource (lib "00") (part "R0603SM"))
    )
    (comp (ref "RC74")
      (value "10Kohm/0603")
      (footprint "R1608-0603")
      (description "10Kohm/1/10W/F/0603")
      (fields (field (name "Comment") "011-103020-0"))
      (libsource (lib "00") (part "R0603SM"))
    )
    (comp (ref "RC75")
      (value "27Kohm/0603")
      (footprint "R0603SM")
      (description "27Kohm/1/10W/F/0603")
      (fields (field (name "Comment") "011-273020-0"))
      (libsource (lib "首航") (part "011-273020-0 R0603SM"))
    )
    (comp (ref "RC76")
      (value "100ohm/0603")
      (footprint "R1608-0603")
      (description "100ohm/1/10W/F/0603")
      (fields (field (name "Comment") "011-101020-0"))
      (libsource (lib "00") (part "R0603SM"))
    )
    (comp (ref "RC79")
      (value "2.7Kohm/0603")
      (footprint "R1608-0603")
      (description "2.7Kohm/1/10W/F/0603")
      (fields (field (name "Comment") "011-272020-0"))
      (libsource (lib "00") (part "R0603SM"))
    )
    (comp (ref "RC83")
      (value "15Kohm/0603")
      (footprint "R1608-0603")
      (description "15Kohm/1/10W/F/0603")
      (fields (field (name "Comment") "011-153020-0"))
      (libsource (lib "00") (part "R0603SM"))
    )
    (comp (ref "RC84")
      (value "4.99Kohm/0603")
      (footprint "R1608-0603")
      (description "4.99Kohm/1/10W/F/0603")
      (fields (field (name "Comment") "011-492020-0"))
      (libsource (lib "00") (part "R0603SM"))
    )
    (comp (ref "RC87")
      (value "100ohm/0603")
      (footprint "R1608-0603")
      (description "100ohm/1/10W/F/0603")
      (fields (field (name "Comment") "011-101020-0"))
      (libsource (lib "00") (part "R0603SM"))
    )
    (comp (ref "RC88")
      (value "10Kohm/0603")
      (footprint "R1608-0603")
      (description "10Kohm/1/10W/F/0603")
      (fields (field (name "Comment") "011-103020-0"))
      (libsource (lib "00") (part "R0603SM"))
    )
    (comp (ref "RC91")
      (value "499ohm/0603")
      (footprint "R1608-0603")
      (description "499ohm/1/10W/F/0603")
      (fields (field (name "Comment") "011-491020-0"))
      (libsource (lib "00") (part "R0603SM"))
    )
    (comp (ref "RC94")
      (value "15Kohm/0603")
      (footprint "R1608-0603")
      (description "15Kohm/1/10W/F/0603")
      (fields (field (name "Comment") "011-153020-0"))
      (libsource (lib "00") (part "R0603SM"))
    )
    (comp (ref "RC99")
      (value "100ohm/0603")
      (footprint "R1608-0603")
      (description "100ohm/1/10W/F/0603")
      (fields (field (name "Comment") "011-101020-0"))
      (libsource (lib "00") (part "R0603SM"))
    )
    (comp (ref "RC100")
      (value "4.99Kohm/0603")
      (footprint "R1608-0603")
      (description "4.99Kohm/1/10W/F/0603")
      (fields (field (name "Comment") "011-492020-0"))
      (libsource (lib "00") (part "R0603SM"))
    )
    (comp (ref "RC101")
      (value "10Kohm/0603")
      (footprint "R1608-0603")
      (description "10Kohm/1/10W/F/0603")
      (fields (field (name "Comment") "011-103020-0"))
      (libsource (lib "00") (part "R0603SM"))
    )
    (comp (ref "RC103")
      (value "40.2Kohm/0603")
      (footprint "R1608-0603")
      (description "40.2Kohm/1/10W/F/0603")
      (fields (field (name "Comment") "011-403020-0"))
      (libsource (lib "00") (part "R0603SM"))
    )
    (comp (ref "RC104")
      (value "4.99Kohm/0603")
      (footprint "R0603SM")
      (description "4.99Kohm/1/10W/F/0603")
      (fields (field (name "Comment") "011-492020-0"))
      (libsource (lib "首航") (part "011-492020-0 R0603SM"))
    )
    (comp (ref "RC105")
      (value "2.7Kohm/0603")
      (footprint "R1608-0603")
      (description "2.7Kohm/1/10W/F/0603")
      (fields (field (name "Comment") "011-272020-0"))
      (libsource (lib "00") (part "R0603SM"))
    )
    (comp (ref "RC106")
      (value "100ohm/0603")
      (footprint "R1608-0603")
      (description "100ohm/1/10W/F/0603")
      (fields (field (name "Comment") "011-101020-0"))
      (libsource (lib "00") (part "R0603SM"))
    )
    (comp (ref "RC107")
      (value "10Kohm/0603")
      (footprint "R1608-0603")
      (description "10Kohm/1/10W/F/0603")
      (fields (field (name "Comment") "011-103020-0"))
      (libsource (lib "00") (part "R0603SM"))
    )
    (comp (ref "RC108")
      (value "1Kohm/0603")
      (footprint "R1608-0603")
      (description "1Kohm/1/10W/F/0603")
      (fields (field (name "Comment") "011-102020-0"))
      (libsource (lib "00") (part "R0603SM"))
    )
    (comp (ref "RC109")
      (value "4.99Kohm/0603")
      (footprint "R1608-0603")
      (description "4.99Kohm/1/10W/F/0603")
      (fields (field (name "Comment") "011-492020-0"))
      (libsource (lib "00") (part "R0603SM"))
    )
    (comp (ref "RC110")
      (value "4.99Kohm/0603")
      (footprint "R1608-0603")
      (description "4.99Kohm/1/10W/F/0603")
      (fields (field (name "Comment") "011-492020-0"))
      (libsource (lib "00") (part "R0603SM"))
    )
    (comp (ref "RC111")
      (value "2.7Kohm/0603")
      (footprint "R1608-0603")
      (description "2.7Kohm/1/10W/F/0603")
      (fields (field (name "Comment") "011-272020-0"))
      (libsource (lib "00") (part "R0603SM"))
    )
    (comp (ref "RC112")
      (value "10Kohm/0603")
      (footprint "R1608-0603")
      (description "10Kohm/1/10W/F/0603")
      (fields (field (name "Comment") "011-103020-0"))
      (libsource (lib "00") (part "R0603SM"))
    )
    (comp (ref "RC113")
      (value "27Kohm/0603")
      (footprint "R0603SM")
      (description "27Kohm/1/10W/F/0603")
      (fields (field (name "Comment") "011-273020-0"))
      (libsource (lib "首航") (part "011-273020-0 R0603SM"))
    )
    (comp (ref "RC114")
      (value "10Kohm/0603")
      (footprint "R1608-0603")
      (description "10Kohm/1/10W/F/0603")
      (fields (field (name "Comment") "011-103020-0"))
      (libsource (lib "*") (part "R0603SM"))
    )
    (comp (ref "RC115")
      (value "5.1Kohm/0603")
      (footprint "R1608-0603")
      (description "5.1Kohm/1/10W/F/0603")
      (fields (field (name "Comment") "011-512020-0"))
      (libsource (lib "00") (part "R0603SM"))
    )
    (comp (ref "RC116")
      (value "4.99Kohm/0603")
      (footprint "R1608-0603")
      (description "4.99Kohm/1/10W/F/0603")
      (fields (field (name "Comment") "011-492020-0"))
      (libsource (lib "00") (part "R0603SM"))
    )
    (comp (ref "RC117")
      (value "4.99Kohm/0603")
      (footprint "R1608-0603")
      (description "4.99Kohm/1/10W/F/0603")
      (fields (field (name "Comment") "011-492020-0"))
      (libsource (lib "00") (part "R0603SM"))
    )
    (comp (ref "RC118")
      (value "4.99Kohm/0603")
      (footprint "R0603SM")
      (description "4.99Kohm/1/10W/F/0603")
      (fields (field (name "Comment") "011-492020-0"))
      (libsource (lib "首航") (part "011-492020-0 R0603SM"))
    )
    (comp (ref "RC119")
      (value "499ohm/0603")
      (footprint "R1608-0603")
      (description "499ohm/1/10W/F/0603")
      (fields (field (name "Comment") "011-491020-0"))
      (libsource (lib "00") (part "R0603SM"))
    )
    (comp (ref "RC122")
      (value "4.99Kohm/0603")
      (footprint "R1608-0603")
      (description "4.99Kohm/1/10W/F/0603")
      (fields (field (name "Comment") "011-492020-0"))
      (libsource (lib "00") (part "R0603SM"))
    )
    (comp (ref "RC124")
      (value "4.99Kohm/0603")
      (footprint "R1608-0603")
      (description "4.99Kohm/1/10W/F/0603")
      (fields (field (name "Comment") "011-492020-0"))
      (libsource (lib "00") (part "R0603SM"))
    )
    (comp (ref "RC125")
      (value "32.4Kohm/0603")
      (footprint "R1608-0603")
      (description "32.4Kohm/1/10W/F/0603")
      (fields (field (name "Comment") "011-323020-0"))
      (libsource (lib "00") (part "R0603SM"))
    )
    (comp (ref "RC126")
      (value "40.2Kohm/0603")
      (footprint "R1608-0603")
      (description "40.2Kohm/1/10W/F/0603")
      (fields (field (name "Comment") "011-403020-0"))
      (libsource (lib "00") (part "R0603SM"))
    )
    (comp (ref "RC127")
      (value "499ohm/0603")
      (footprint "R1608-0603")
      (description "499ohm/1/10W/F/0603")
      (fields (field (name "Comment") "011-491020-0"))
      (libsource (lib "00") (part "R0603SM"))
    )
    (comp (ref "RC128")
      (value "2.7Kohm/0603")
      (footprint "R1608-0603")
      (description "2.7Kohm/1/10W/F/0603")
      (fields (field (name "Comment") "011-272020-0"))
      (libsource (lib "00") (part "R0603SM"))
    )
    (comp (ref "RC129")
      (value "20Kohm/0603")
      (footprint "R1608-0603")
      (description "20Kohm/1/10W/F/0603")
      (fields (field (name "Comment") "011-203020-0"))
      (libsource (lib "00") (part "R0603SM"))
    )
    (comp (ref "RC130")
      (value "0ohm/0603")
      (footprint "R1608-0603")
      (description "0ohm/1/10W/F/0603")
      (fields (field (name "Comment") "011-000020-0"))
      (libsource (lib "") (part "R0603SM_1"))
    )
    (comp (ref "RC131")
      (value "1Kohm/0603")
      (footprint "R1608-0603")
      (description "1Kohm/1/10W/F/0603")
      (fields (field (name "Comment") "011-102020-0"))
      (libsource (lib "00") (part "R0603SM"))
    )
    (comp (ref "RC132")
      (value "4.99Kohm/0603")
      (footprint "R1608-0603")
      (description "4.99Kohm/1/10W/F/0603")
      (fields (field (name "Comment") "011-492020-0"))
      (libsource (lib "00") (part "R0603SM"))
    )
    (comp (ref "RC133")
      (value "10Kohm/0603")
      (footprint "R1608-0603")
      (description "10Kohm/1/10W/F/0603")
      (fields (field (name "Comment") "011-103020-0"))
      (libsource (lib "*") (part "R0603SM"))
    )
    (comp (ref "RC134") (value "NC") (footprint "R1608-0603") (libsource (lib "00") (part "R0603SM")))
    (comp (ref "RC135")
      (value "4.99Kohm/0603")
      (footprint "R1608-0603")
      (description "4.99Kohm/1/10W/F/0603")
      (fields (field (name "Comment") "011-492020-0"))
      (libsource (lib "00") (part "R0603SM"))
    )
    (comp (ref "RC136")
      (value "27Kohm/0603")
      (footprint "R0603SM")
      (description "27Kohm/1/10W/F/0603")
      (fields (field (name "Comment") "011-273020-0"))
      (libsource (lib "首航") (part "011-273020-0 R0603SM"))
    )
    (comp (ref "RC137")
      (value "499ohm/0603")
      (footprint "R1608-0603")
      (description "499ohm/1/10W/F/0603")
      (fields (field (name "Comment") "011-491020-0"))
      (libsource (lib "00") (part "R0603SM"))
    )
    (comp (ref "RC138")
      (value "300Kohm/0603")
      (footprint "R1608-0603")
      (description "300Kohm/1/10W/F/0603")
      (fields (field (name "Comment") "011-304021-0"))
      (libsource (lib "00") (part "R0603SM"))
    )
    (comp (ref "RC139")
      (value "300Kohm/0603")
      (footprint "R1608-0603")
      (description "300Kohm/1/10W/F/0603")
      (fields (field (name "Comment") "011-304021-0"))
      (libsource (lib "00") (part "R0603SM"))
    )
    (comp (ref "RC140")
      (value "10Kohm/0603")
      (footprint "R1608-0603")
      (description "10Kohm/1/10W/F/0603")
      (fields (field (name "Comment") "011-103020-0"))
      (libsource (lib "00") (part "R0603SM"))
    )
    (comp (ref "RC142")
      (value "40.2Kohm/0603")
      (footprint "R1608-0603")
      (description "40.2Kohm/1/10W/F/0603")
      (fields (field (name "Comment") "011-403020-0"))
      (libsource (lib "00") (part "R0603SM"))
    )
    (comp (ref "RC143")
      (value "10Kohm/0603")
      (footprint "R1608-0603")
      (description "10Kohm/1/10W/F/0603")
      (fields (field (name "Comment") "011-103020-0"))
      (libsource (lib "*") (part "R0603SM"))
    )
    (comp (ref "RC144")
      (value "10Kohm/0603")
      (footprint "R1608-0603")
      (description "10Kohm/1/10W/F/0603")
      (fields (field (name "Comment") "011-103020-0"))
      (libsource (lib "*") (part "R0603SM"))
    )
    (comp (ref "RC145")
      (value "4.99Kohm/0603")
      (footprint "R1608-0603")
      (description "4.99Kohm/1/10W/F/0603")
      (fields (field (name "Comment") "011-492020-0"))
      (libsource (lib "00") (part "R0603SM"))
    )
    (comp (ref "RC146")
      (value "2.7Kohm/0603")
      (footprint "R1608-0603")
      (description "2.7Kohm/1/10W/F/0603")
      (fields (field (name "Comment") "011-272020-0"))
      (libsource (lib "00") (part "R0603SM"))
    )
    (comp (ref "RC147")
      (value "10Kohm/0603")
      (footprint "R1608-0603")
      (description "10Kohm/1/10W/F/0603")
      (fields (field (name "Comment") "011-103020-0"))
      (libsource (lib "*") (part "R0603SM"))
    )
    (comp (ref "RC149")
      (value "499ohm/0603")
      (footprint "R1608-0603")
      (description "499ohm/1/10W/F/0603")
      (fields (field (name "Comment") "011-491020-0"))
      (libsource (lib "00") (part "R0603SM"))
    )
    (comp (ref "RC150")
      (value "4.7Kohm/0603")
      (footprint "R1608-0603")
      (description "4.7Kohm/1/10W/F/0603")
      (fields (field (name "Comment") "011-472020-0"))
      (libsource (lib "*") (part "R0603SM_7"))
    )
    (comp (ref "RC151")
      (value "4.99Kohm/0603")
      (footprint "R1608-0603")
      (description "4.99Kohm/1/10W/F/0603")
      (fields (field (name "Comment") "011-492020-0"))
      (libsource (lib "00") (part "R0603SM"))
    )
    (comp (ref "RC152")
      (value "40.2Kohm/0603")
      (footprint "R1608-0603")
      (description "40.2Kohm/1/10W/F/0603")
      (fields (field (name "Comment") "011-403020-0"))
      (libsource (lib "00") (part "R0603SM"))
    )
    (comp (ref "RC157")
      (value "10Kohm/0603")
      (footprint "R1608-0603")
      (description "10Kohm/1/10W/F/0603")
      (fields (field (name "Comment") "011-103020-0"))
      (libsource (lib "00") (part "R0603SM"))
    )
    (comp (ref "RC158")
      (value "10Kohm/0603")
      (footprint "R1608-0603")
      (description "10Kohm/1/10W/F/0603")
      (fields (field (name "Comment") "011-103020-0"))
      (libsource (lib "00") (part "R0603SM"))
    )
    (comp (ref "RC161")
      (value "4.7Kohm/0603")
      (footprint "R1608-0603")
      (description "4.7Kohm/1/10W/F/0603")
      (fields (field (name "Comment") "011-472020-0"))
      (libsource (lib "00") (part "R0603SM"))
    )
    (comp (ref "RC162")
      (value "4.7Kohm/0603*4")
      (footprint "RN0603*4")
      (description "4.7Kohm/J/0603*4")
      (fields (field (name "Comment") "019-472000-0"))
      (libsource (lib "00") (part "R0603*4SM"))
    )
    (comp (ref "RC163")
      (value "4.99Kohm/0603")
      (footprint "R1608-0603")
      (description "4.99Kohm/1/10W/F/0603")
      (fields (field (name "Comment") "011-492020-0"))
      (libsource (lib "00") (part "R0603SM"))
    )
    (comp (ref "RC164")
      (value "1Kohm/0603")
      (footprint "R1608-0603")
      (description "1Kohm/1/10W/F/0603")
      (fields (field (name "Comment") "011-102020-0"))
      (libsource (lib "00") (part "R0603SM"))
    )
    (comp (ref "RC165")
      (value "10Kohm/0603")
      (footprint "R1608-0603")
      (description "10Kohm/1/10W/F/0603")
      (fields (field (name "Comment") "011-103020-0"))
      (libsource (lib "00") (part "R0603SM"))
    )
    (comp (ref "RC166")
      (value "2.7Kohm/0603")
      (footprint "R1608-0603")
      (description "2.7Kohm/1/10W/F/0603")
      (fields (field (name "Comment") "011-272020-0"))
      (libsource (lib "00") (part "R0603SM"))
    )
    (comp (ref "RC167")
      (value "4.99Kohm/0603")
      (footprint "R1608-0603")
      (description "4.99Kohm/1/10W/F/0603")
      (fields (field (name "Comment") "011-492020-0"))
      (libsource (lib "00") (part "R0603SM"))
    )
    (comp (ref "RC168")
      (value "4.99Kohm/0603")
      (footprint "R1608-0603")
      (description "4.99Kohm/1/10W/F/0603")
      (fields (field (name "Comment") "011-492020-0"))
      (libsource (lib "00") (part "R0603SM"))
    )
    (comp (ref "RC169")
      (value "4.99Kohm/0603")
      (footprint "R1608-0603")
      (description "4.99Kohm/1/10W/F/0603")
      (fields (field (name "Comment") "011-492020-0"))
      (libsource (lib "00") (part "R0603SM"))
    )
    (comp (ref "RC170")
      (value "4.7Kohm/0603")
      (footprint "R1608-0603")
      (description "4.7Kohm/1/10W/F/0603")
      (fields (field (name "Comment") "011-472020-0"))
      (libsource (lib "00") (part "R0603SM"))
    )
    (comp (ref "RC171")
      (value "2.7Kohm/0603")
      (footprint "R1608-0603")
      (description "2.7Kohm/1/10W/F/0603")
      (fields (field (name "Comment") "011-272020-0"))
      (libsource (lib "00") (part "R0603SM"))
    )
    (comp (ref "RC172")
      (value "1Kohm/0603")
      (footprint "R1608-0603")
      (description "1Kohm/1/10W/F/0603")
      (fields (field (name "Comment") "011-102020-0"))
      (libsource (lib "00") (part "R0603SM"))
    )
    (comp (ref "RC173")
      (value "011-472020-0")
      (footprint "R1608-0603")
      (description "4.7Kohm/1/10W/F/0603")
      (fields (field (name "ALTIUM_VALUE") "4.7Kohm/0603"))
      (libsource (lib "00") (part "R0603SM"))
    )
    (comp (ref "RC174")
      (value "4.99Kohm/0603")
      (footprint "R1608-0603")
      (description "4.99Kohm/1/10W/F/0603")
      (fields (field (name "Comment") "011-492020-0"))
      (libsource (lib "00") (part "R0603SM"))
    )
    (comp (ref "RC175")
      (value "2.7Kohm/0603")
      (footprint "R1608-0603")
      (description "2.7Kohm/1/10W/F/0603")
      (fields (field (name "Comment") "011-272020-0"))
      (libsource (lib "00") (part "R0603SM"))
    )
    (comp (ref "RC176")
      (value "1Kohm/0603")
      (footprint "R1608-0603")
      (description "1Kohm/1/10W/F/0603")
      (fields (field (name "Comment") "011-102020-0"))
      (libsource (lib "00") (part "R0603SM"))
    )
    (comp (ref "RC177")
      (value "4.99Kohm/0603")
      (footprint "R1608-0603")
      (description "4.99Kohm/1/10W/F/0603")
      (fields (field (name "Comment") "011-492020-0"))
      (libsource (lib "00") (part "R0603SM"))
    )
    (comp (ref "RC178")
      (value "10Kohm/0603")
      (footprint "R1608-0603")
      (description "10Kohm/1/10W/F/0603")
      (fields (field (name "Comment") "011-103020-0"))
      (libsource (lib "00") (part "R0603SM"))
    )
    (comp (ref "RC179")
      (value "10Kohm/0603")
      (footprint "R1608-0603")
      (description "10Kohm/1/10W/F/0603")
      (fields (field (name "Comment") "011-103020-0"))
      (libsource (lib "00") (part "R0603SM"))
    )
    (comp (ref "RC180")
      (value "4.99Kohm/0603")
      (footprint "R1608-0603")
      (description "4.99Kohm/1/10W/F/0603")
      (fields (field (name "Comment") "011-492020-0"))
      (libsource (lib "00") (part "R0603SM"))
    )
    (comp (ref "RC181")
      (value "4.99Kohm/0603")
      (footprint "R1608-0603")
      (description "4.99Kohm/1/10W/F/0603")
      (fields (field (name "Comment") "011-492020-0"))
      (libsource (lib "00") (part "R0603SM"))
    )
    (comp (ref "RC182")
      (value "499Kohm/1206")
      (footprint "R3216-1206")
      (description "499Kohm/1/4W/F/1206")
      (fields (field (name "Comment") "011-494050-0"))
      (libsource (lib "RES") (part "R1206SM-499K"))
    )
    (comp (ref "RC183")
      (value "2.7Kohm/0603")
      (footprint "R1608-0603")
      (description "2.7Kohm/1/10W/F/0603")
      (fields (field (name "Comment") "011-272020-0"))
      (libsource (lib "00") (part "R0603SM"))
    )
    (comp (ref "RC184")
      (value "4.99Kohm/0603")
      (footprint "R1608-0603")
      (description "4.99Kohm/1/10W/F/0603")
      (fields (field (name "Comment") "011-492020-0"))
      (libsource (lib "00") (part "R0603SM"))
    )
    (comp (ref "RC185")
      (value "5Mohm/1W/F")
      (footprint "R3W-S")
      (fields (field (name "Comment") "013-515220-1"))
      (libsource (lib "RES") (part "R3W-1K"))
    )
    (comp (ref "RC186")
      (value "1Kohm/0603")
      (footprint "R1608-0603")
      (description "1Kohm/1/10W/F/0603")
      (fields (field (name "Comment") "011-102020-0"))
      (libsource (lib "00") (part "R0603SM"))
    )
    (comp (ref "RC187")
      (value "2.7Kohm/0603")
      (footprint "R1608-0603")
      (description "2.7Kohm/1/10W/F/0603")
      (fields (field (name "Comment") "011-272020-0"))
      (libsource (lib "00") (part "R0603SM"))
    )
    (comp (ref "RC188")
      (value "33Kohm/0603")
      (footprint "R1608-0603")
      (description "33Kohm/1/10W/F/0603")
      (fields (field (name "Comment") "011-333020-0"))
      (libsource (lib "00") (part "R0603SM"))
    )
    (comp (ref "RC189")
      (value "2.7Kohm/0603")
      (footprint "R1608-0603")
      (description "2.7Kohm/1/10W/F/0603")
      (fields (field (name "Comment") "011-272020-0"))
      (libsource (lib "00") (part "R0603SM"))
    )
    (comp (ref "RC190")
      (value "1Kohm/0603")
      (footprint "R1608-0603")
      (description "1Kohm/1/10W/F/0603")
      (fields (field (name "Comment") "011-102020-0"))
      (libsource (lib "00") (part "R0603SM"))
    )
    (comp (ref "RC191")
      (value "4.99Kohm/0603")
      (footprint "R1608-0603")
      (description "4.99Kohm/1/10W/F/0603")
      (fields (field (name "Comment") "011-492020-0"))
      (libsource (lib "00") (part "R0603SM"))
    )
    (comp (ref "RC192")
      (value "10Kohm/0603")
      (footprint "R1608-0603")
      (description "10Kohm/1/10W/F/0603")
      (fields (field (name "Comment") "011-103020-0"))
      (libsource (lib "00") (part "R0603SM"))
    )
    (comp (ref "RC193")
      (value "4.7Kohm/0603")
      (footprint "R1608-0603")
      (description "4.7Kohm/1/10W/F/0603")
      (fields (field (name "Comment") "011-472020-0"))
      (libsource (lib "00") (part "R0603SM"))
    )
    (comp (ref "RC194")
      (value "4.7Kohm/0603")
      (footprint "R1608-0603")
      (description "4.7Kohm/1/10W/F/0603")
      (fields (field (name "Comment") "011-472020-0"))
      (libsource (lib "00") (part "R0603SM"))
    )
    (comp (ref "RC195")
      (value "5Mohm/1W/F")
      (footprint "R3W-S")
      (fields (field (name "Comment") "013-515220-1"))
      (libsource (lib "RES") (part "R3W-1K"))
    )
    (comp (ref "RC196")
      (value "1Kohm/0603")
      (footprint "R1608-0603")
      (description "1Kohm/1/10W/F/0603")
      (fields (field (name "Comment") "011-102020-0"))
      (libsource (lib "00") (part "R0603SM"))
    )
    (comp (ref "RC197")
      (value "1Kohm/0603")
      (footprint "R1608-0603")
      (description "1Kohm/1/10W/F/0603")
      (fields (field (name "Comment") "011-102020-0"))
      (libsource (lib "00") (part "R0603SM"))
    )
    (comp (ref "RC198")
      (value "10Kohm/0603")
      (footprint "R1608-0603")
      (description "10Kohm/1/10W/F/0603")
      (fields (field (name "Comment") "011-103020-0"))
      (libsource (lib "00") (part "R0603SM"))
    )
    (comp (ref "RC199")
      (value "4.99Kohm/0603")
      (footprint "R1608-0603")
      (description "4.99Kohm/1/10W/F/0603")
      (fields (field (name "Comment") "011-492020-0"))
      (libsource (lib "00") (part "R0603SM"))
    )
    (comp (ref "RC200")
      (value "4.99Kohm/0603")
      (footprint "R1608-0603")
      (description "4.99Kohm/1/10W/F/0603")
      (fields (field (name "Comment") "011-492020-0"))
      (libsource (lib "00") (part "R0603SM"))
    )
    (comp (ref "RC201")
      (value "4.99Kohm/0603")
      (footprint "R1608-0603")
      (description "4.99Kohm/1/10W/F/0603")
      (fields (field (name "Comment") "011-492020-0"))
      (libsource (lib "00") (part "R0603SM"))
    )
    (comp (ref "RC202")
      (value "4.99Kohm/0603")
      (footprint "R1608-0603")
      (description "4.99Kohm/1/10W/F/0603")
      (fields (field (name "Comment") "011-492020-0"))
      (libsource (lib "00") (part "R0603SM"))
    )
    (comp (ref "RC203")
      (value "10Kohm/0603")
      (footprint "R1608-0603")
      (description "10Kohm/1/10W/F/0603")
      (fields (field (name "Comment") "011-103020-0"))
      (libsource (lib "00") (part "R0603SM"))
    )
    (comp (ref "RC506")
      (value "200Kohm/0603")
      (footprint "R1608-0603")
      (description "200Kohm/1/10W/F/0603")
      (fields (field (name "Comment") "011-204020-0"))
      (libsource (lib "00") (part "R0603SM"))
    )
    (comp (ref "RC507")
      (value "200Kohm/0603")
      (footprint "R1608-0603")
      (description "200Kohm/1/10W/F/0603")
      (fields (field (name "Comment") "011-204020-0"))
      (libsource (lib "00") (part "R0603SM"))
    )
    (comp (ref "RC511")
      (value "130Kohm/0603")
      (footprint "R1608-0603")
      (description "130Kohm/1/10W/F/0603")
      (fields (field (name "Comment") "011-131020-0"))
      (libsource (lib "00") (part "R0603SM"))
    )
    (comp (ref "RC532")
      (value "4.7Kohm/0603")
      (footprint "R1608-0603")
      (description "4.7Kohm/1/10W/F/0603")
      (fields (field (name "Comment") "011-472020-0"))
      (libsource (lib "*") (part "R0603SM_7"))
    )
    (comp (ref "RC533")
      (value "4.7Kohm/0603")
      (footprint "R1608-0603")
      (description "4.7Kohm/1/10W/F/0603")
      (fields (field (name "Comment") "011-472020-0"))
      (libsource (lib "*") (part "R0603SM_7"))
    )
    (comp (ref "RC534")
      (value "1Kohm/0603")
      (footprint "R1608-0603")
      (description "1Kohm/1/10W/F/0603")
      (fields (field (name "Comment") "011-102020-0"))
      (libsource (lib "00") (part "R0603SM"))
    )
    (comp (ref "RC535")
      (value "4.7Kohm/0603")
      (footprint "R1608-0603")
      (description "4.7Kohm/1/10W/F/0603")
      (fields (field (name "Comment") "011-472020-0"))
      (libsource (lib "*") (part "R0603SM_7"))
    )
    (comp (ref "RC593")
      (value "499Kohm/1206")
      (footprint "R3216-1206")
      (description "499Kohm/1/4W/F/1206")
      (fields (field (name "Comment") "011-494050-0"))
      (libsource (lib "RES") (part "R1206SM-499K"))
    )
    (comp (ref "RC706")
      (value "4.7Kohm/0603")
      (footprint "R1608-0603")
      (description "4.7Kohm/1/10W/F/0603")
      (fields (field (name "Comment") "011-472020-0"))
      (libsource (lib "00") (part "R0603SM"))
    )
    (comp (ref "RC707")
      (value "33Kohm/0603")
      (footprint "R1608-0603")
      (description "33Kohm/1/10W/F/0603")
      (fields (field (name "Comment") "011-333020-0"))
      (libsource (lib "00") (part "R0603SM"))
    )
    (comp (ref "RC708")
      (value "33Kohm/0603")
      (footprint "R1608-0603")
      (description "33Kohm/1/10W/F/0603")
      (fields (field (name "Comment") "011-333020-0"))
      (libsource (lib "00") (part "R0603SM"))
    )
    (comp (ref "RC709")
      (value "33Kohm/0603")
      (footprint "R1608-0603")
      (description "33Kohm/1/10W/F/0603")
      (fields (field (name "Comment") "011-333020-0"))
      (libsource (lib "00") (part "R0603SM"))
    )
    (comp (ref "RC710")
      (value "33Kohm/0603")
      (footprint "R1608-0603")
      (description "33Kohm/1/10W/F/0603")
      (fields (field (name "Comment") "011-333020-0"))
      (libsource (lib "00") (part "R0603SM"))
    )
    (comp (ref "SC6")
      (value "SC40(M4)")
      (footprint "SC50_M4-GND")
      (description "SC50M4")
      (libsource (lib "zcp") (part "SC50_M4-GND"))
    )
    (comp (ref "TP2") (value "NC") (footprint "TEST-12") (libsource (lib "00") (part "17K TPD")))
    (comp (ref "TP3") (value "NC") (footprint "TEST-12") (libsource (lib "00") (part "17K TPD")))
    (comp (ref "TP4") (value "NC") (footprint "TEST-12") (libsource (lib "00") (part "17K TPD")))
    (comp (ref "TP5") (value "NC") (footprint "TEST-12") (libsource (lib "00") (part "17K TPD")))
    (comp (ref "TP8") (value "NC") (footprint "TEST-12") (libsource (lib "00") (part "17K TPD")))
    (comp (ref "TP9") (value "NC") (footprint "TEST-12") (libsource (lib "00") (part "17K TPD")))
    (comp (ref "TP10") (value "NC") (footprint "TEST-12") (libsource (lib "00") (part "17K TPD")))
    (comp (ref "TP12") (value "NC") (footprint "TEST-12") (libsource (lib "00") (part "17K TPD")))
    (comp (ref "TP13") (value "NC") (footprint "TEST-12") (libsource (lib "00") (part "17K TPD")))
    (comp (ref "TP14") (value "NC") (footprint "TEST-12") (libsource (lib "00") (part "17K TPD")))
    (comp (ref "TP15") (value "NC") (footprint "TEST-12") (libsource (lib "00") (part "17K TPD")))
    (comp (ref "TP17") (value "NC") (footprint "TEST-12") (libsource (lib "00") (part "17K TPD")))
    (comp (ref "TP18") (value "NC") (footprint "TEST-12") (libsource (lib "00") (part "17K TPD")))
    (comp (ref "TP19") (value "NC") (footprint "TEST-12") (libsource (lib "00") (part "17K TPD")))
    (comp (ref "TP20") (value "NC") (footprint "TEST-12") (libsource (lib "00") (part "17K TPD")))
    (comp (ref "TP24") (value "NC") (footprint "TEST-12") (libsource (lib "00") (part "17K TPD")))
    (comp (ref "UC12")
      (value "SPX1117M3-L-1-5/TR")
      (footprint "SOT223")
      (description "Low Dropout Regulator/SOT-223-3")
      (fields (field (name "Comment") "050-210000-0"))
      (libsource (lib "首航") (part "050-210000-0 SOT223"))
    )
    (comp (ref "UC14")
      (value "MC14052BDR2G")
      (footprint "SO16")
      (description "Analog Multiplexer/Demultiplexer/SOIC-16")
      (fields (field (name "Comment") "050-610312-0"))
      (libsource (lib "00") (part "IC 14052BSM"))
    )
    (comp (ref "UC16")
      (value "MC14052BDR2G")
      (footprint "SO16")
      (description "Analog Multiplexer/Demultiplexer/SOIC-16")
      (fields (field (name "Comment") "050-610312-0"))
      (libsource (lib "00") (part "IC 14052BSM"))
    )
    (comp (ref "UC50")
      (value "050-510021-0")
      (footprint "SO14")
      (description "Quad 2-Input NAND Gate/SO-14")
      (fields (field (name "ALTIUM_UNNAMED_1") "DM74LS00M"))
      (libsource (lib "*") (part "74LS00"))
    )
    (comp (ref "UC624")
      (value "TL074IDR")
      (footprint "SO14")
      (description "Operational Amplifier/SOIC-14")
      (fields (field (name "Comment") "050-612020-0"))
      (libsource (lib "00") (part "IC TL074SM"))
    )
    (comp (ref "UC625")
      (value "TL072IDR")
      (footprint "SO8")
      (description "Operational Amplifiers/SO-8")
      (fields (field (name "Comment") "050-610000-0"))
      (libsource (lib "01") (part "IC TL072SM"))
    )
    (comp (ref "UC626")
      (value "LM2903MX")
      (footprint "SO8")
      (description "Voltage Dual Comparator/SOIC-8")
      (fields (field (name "Comment") "050-610040-0"))
      (libsource (lib "00") (part "IC 2903TSM"))
    )
    (comp (ref "UC627")
      (value "TL074IDR")
      (footprint "SO14")
      (description "Operational Amplifier/SOIC-14")
      (fields (field (name "Comment") "050-612020-0"))
      (libsource (lib "00") (part "IC TL074SM"))
    )
    (comp (ref "UC629")
      (value "TL074IDR")
      (footprint "SO14")
      (description "Operational Amplifier/SOIC-14")
      (fields (field (name "Comment") "050-612020-0"))
      (libsource (lib "00") (part "IC TL074SM"))
    )
    (comp (ref "UC630")
      (value "TL074IDR")
      (footprint "SO14")
      (description "Operational Amplifier/SOIC-14")
      (fields (field (name "Comment") "050-612020-0"))
      (libsource (lib "00") (part "IC TL074SM"))
    )
    (comp (ref "UC632")
      (value "TL074IDR")
      (footprint "SO14")
      (description "Operational Amplifier/SOIC-14")
      (fields (field (name "Comment") "050-612020-0"))
      (libsource (lib "00") (part "IC TL074SM"))
    )
    (comp (ref "UC633")
      (value "TL074IDR")
      (footprint "SO14")
      (description "Operational Amplifier/SOIC-14")
      (fields (field (name "Comment") "050-612020-0"))
      (libsource (lib "00") (part "IC TL074SM"))
    )
    (comp (ref "UC634")
      (value "TL074IDR")
      (footprint "SO14")
      (description "Operational Amplifier/SOIC-14")
      (fields (field (name "Comment") "050-612020-0"))
      (libsource (lib "00") (part "IC TL074SM"))
    )
    (comp (ref "UC635")
      (value "TL074IDR")
      (footprint "SO14")
      (description "Operational Amplifier/SOIC-14")
      (fields (field (name "Comment") "050-612020-0"))
      (libsource (lib "00") (part "IC TL074SM"))
    )
    (comp (ref "UC636")
      (value "LM239DR")
      (footprint "SO14")
      (description "Quad Differential Comparator/SOIC-14")
      (fields (field (name "Comment") "050-610030-0"))
      (libsource (lib "") (part "IC 239SM_1"))
    )
    (comp (ref "UC637")
      (value "TL074IDR")
      (footprint "SO14")
      (description "Operational Amplifier/SOIC-14")
      (fields (field (name "Comment") "050-612020-0"))
      (libsource (lib "00") (part "IC TL074SM"))
    )
    (comp (ref "UC638")
      (value "TL074IDR")
      (footprint "SO14")
      (description "Operational Amplifier/SOIC-14")
      (fields (field (name "Comment") "050-612020-0"))
      (libsource (lib "00") (part "IC TL074SM"))
    )
  )
  (nets
    (net (code "1") (name "+5V") (class "Default")
      (node (ref "CC84") (pin "2") (pinfunction "2_2") (pintype "passive"))
      (node (ref "CC95") (pin "2") (pinfunction "2_2") (pintype "passive"))
      (node (ref "RC115") (pin "2") (pinfunction "2_2") (pintype "passive"))
      (node (ref "UC14") (pin "16") (pinfunction "16_16") (pintype "power_in"))
      (node (ref "UC16") (pin "16") (pinfunction "16_16") (pintype "power_in"))
    )
    (net (code "2") (name "+12V") (class "Default")
      (node (ref "CC16") (pin "1") (pinfunction "1_1") (pintype "passive"))
      (node (ref "CC178") (pin "1") (pinfunction "1_1") (pintype "passive"))
      (node (ref "CC18") (pin "1") (pinfunction "1_1") (pintype "passive"))
      (node (ref "CC19") (pin "2") (pinfunction "2_2") (pintype "passive"))
      (node (ref "CC21") (pin "1") (pinfunction "1_1") (pintype "passive"))
      (node (ref "CC216") (pin "2") (pinfunction "2_2") (pintype "passive"))
      (node (ref "CC277") (pin "1") (pinfunction "1_1") (pintype "passive"))
      (node (ref "CC55") (pin "2") (pinfunction "2_2") (pintype "passive"))
      (node (ref "CC63") (pin "1") (pinfunction "1_1") (pintype "passive"))
      (node (ref "CC77") (pin "1") (pinfunction "1_1") (pintype "passive"))
      (node (ref "CC78") (pin "2") (pinfunction "2_2") (pintype "passive"))
      (node (ref "CC82") (pin "1") (pinfunction "1_1") (pintype "passive"))
      (node (ref "CC87") (pin "1") (pinfunction "1_1") (pintype "passive"))
      (node (ref "CC9") (pin "1") (pinfunction "1_1") (pintype "passive"))
      (node (ref "RC129") (pin "2") (pinfunction "2_2") (pintype "passive"))
      (node (ref "RC511") (pin "2") (pinfunction "2_2") (pintype "passive"))
      (node (ref "UC12") (pin "3") (pinfunction "Vin_3") (pintype "passive"))
      (node (ref "UC624") (pin "4") (pinfunction "4_4") (pintype "passive"))
      (node (ref "UC625") (pin "8") (pinfunction "+15V_8") (pintype "passive"))
      (node (ref "UC626") (pin "8") (pinfunction "8_8") (pintype "power_in"))
      (node (ref "UC627") (pin "4") (pinfunction "4_4") (pintype "passive"))
      (node (ref "UC629") (pin "4") (pinfunction "4_4") (pintype "passive"))
      (node (ref "UC630") (pin "4") (pinfunction "4_4") (pintype "passive"))
      (node (ref "UC632") (pin "4") (pinfunction "4_4") (pintype "passive"))
      (node (ref "UC633") (pin "4") (pinfunction "4_4") (pintype "passive"))
      (node (ref "UC634") (pin "4") (pinfunction "4_4") (pintype "passive"))
      (node (ref "UC635") (pin "4") (pinfunction "4_4") (pintype "passive"))
      (node (ref "UC636") (pin "3") (pinfunction "3_3") (pintype "passive"))
      (node (ref "UC637") (pin "4") (pinfunction "4_4") (pintype "passive"))
      (node (ref "UC638") (pin "4") (pinfunction "4_4") (pintype "passive"))
    )
    (net (code "3") (name "-12V") (class "Default")
      (node (ref "CC15") (pin "1") (pinfunction "1_1") (pintype "passive"))
      (node (ref "CC17") (pin "1") (pinfunction "1_1") (pintype "passive"))
      (node (ref "CC177") (pin "1") (pinfunction "1_1") (pintype "passive"))
      (node (ref "CC20") (pin "1") (pinfunction "1_1") (pintype "passive"))
      (node (ref "CC280") (pin "1") (pinfunction "1_1") (pintype "passive"))
      (node (ref "CC62") (pin "1") (pinfunction "1_1") (pintype "passive"))
      (node (ref "CC72") (pin "2") (pinfunction "2_2") (pintype "passive"))
      (node (ref "CC76") (pin "1") (pinfunction "1_1") (pintype "passive"))
      (node (ref "CC8") (pin "1") (pinfunction "1_1") (pintype "passive"))
      (node (ref "CC88") (pin "1") (pinfunction "1_1") (pintype "passive"))
      (node (ref "CC90") (pin "2") (pinfunction "2_2") (pintype "passive"))
      (node (ref "UC624") (pin "11") (pinfunction "11_11") (pintype "passive"))
      (node (ref "UC625") (pin "4") (pinfunction "-15V_4") (pintype "passive"))
      (node (ref "UC627") (pin "11") (pinfunction "11_11") (pintype "passive"))
      (node (ref "UC629") (pin "11") (pinfunction "11_11") (pintype "passive"))
      (node (ref "UC630") (pin "11") (pinfunction "11_11") (pintype "passive"))
      (node (ref "UC632") (pin "11") (pinfunction "11_11") (pintype "passive"))
      (node (ref "UC633") (pin "11") (pinfunction "11_11") (pintype "passive"))
      (node (ref "UC634") (pin "11") (pinfunction "11_11") (pintype "passive"))
      (node (ref "UC635") (pin "11") (pinfunction "11_11") (pintype "passive"))
      (node (ref "UC637") (pin "11") (pinfunction "11_11") (pintype "passive"))
      (node (ref "UC638") (pin "11") (pinfunction "11_11") (pintype "passive"))
    )
    (net (code "4") (name "/DSP_BusOVP") (class "Default")
      (node (ref "DC9") (pin "2") (pinfunction "2_2") (pintype "passive"))
      (node (ref "RC110") (pin "2") (pinfunction "2_2") (pintype "passive"))
      (node (ref "TP15") (pin "1") (pinfunction "1_1") (pintype "passive"))
      (node (ref "UC626") (pin "1") (pinfunction "1_1") (pintype "passive"))
      (node (ref "UC626") (pin "7") (pinfunction "1_7") (pintype "passive"))
    )
    (net (code "5") (name "/GFCI") (class "Default")
      (node (ref "RC163") (pin "1") (pinfunction "1_1") (pintype "passive"))
      (node (ref "RC174") (pin "1") (pinfunction "1_1") (pintype "passive"))
    )
    (net (code "6") (name "/IgridMAX") (class "Default")
      (node (ref "CC64") (pin "2") (pinfunction "2_2") (pintype "passive"))
      (node (ref "DC1") (pin "2") (pinfunction "2_2") (pintype "passive"))
      (node (ref "DC2") (pin "2") (pinfunction "2_2") (pintype "passive"))
      (node (ref "DC6") (pin "2") (pinfunction "2_2") (pintype "passive"))
      (node (ref "RC114") (pin "2") (pinfunction "2_2") (pintype "passive"))
      (node (ref "RC133") (pin "2") (pinfunction "2_2") (pintype "passive"))
    )
    (net (code "7") (name "/IgridMIN") (class "Default")
      (node (ref "CC71") (pin "1") (pinfunction "1_1") (pintype "passive"))
      (node (ref "DC1") (pin "1") (pinfunction "1_1") (pintype "passive"))
      (node (ref "DC2") (pin "1") (pinfunction "1_1") (pintype "passive"))
      (node (ref "DC6") (pin "1") (pinfunction "1_1") (pintype "passive"))
      (node (ref "RC144") (pin "1") (pinfunction "1_1") (pintype "passive"))
      (node (ref "RC147") (pin "2") (pinfunction "2_2") (pintype "passive"))
    )
    (net (code "8") (name "/IgridR") (class "Default")
      (node (ref "RC18") (pin "1") (pinfunction "1_1") (pintype "passive"))
    )
    (net (code "9") (name "/IgridR+") (class "Default")
      (node (ref "RC24") (pin "2") (pinfunction "2_2") (pintype "passive"))
    )
    (net (code "10") (name "/IgridR-") (class "Default")
      (node (ref "RC42") (pin "2") (pinfunction "2_2") (pintype "passive"))
    )
    (net (code "11") (name "/IgridS") (class "Default")
      (node (ref "RC91") (pin "1") (pinfunction "1_1") (pintype "passive"))
    )
    (net (code "12") (name "/IgridS+") (class "Default")
      (node (ref "RC99") (pin "2") (pinfunction "2_2") (pintype "passive"))
    )
    (net (code "13") (name "/IgridS-") (class "Default")
      (node (ref "RC106") (pin "2") (pinfunction "2_2") (pintype "passive"))
    )
    (net (code "14") (name "/IgridT") (class "Default")
      (node (ref "RC16") (pin "1") (pinfunction "1_1") (pintype "passive"))
    )
    (net (code "15") (name "/IgridT+") (class "Default")
      (node (ref "RC23") (pin "2") (pinfunction "2_2") (pintype "passive"))
    )
    (net (code "16") (name "/IgridT-") (class "Default")
      (node (ref "RC34") (pin "2") (pinfunction "2_2") (pintype "passive"))
    )
    (net (code "17") (name "/Ipv1") (class "Default")
      (node (ref "CC446") (pin "1") (pinfunction "1_1") (pintype "passive"))
      (node (ref "UC634") (pin "1") (pintype "passive"))
      (node (ref "UC634") (pin "2") (pintype "passive"))
    )
    (net (code "18") (name "/Ipv1-P") (class "Default")
      (node (ref "CC39") (pin "1") (pinfunction "1_1") (pintype "passive"))
      (node (ref "RC60") (pin "2") (pinfunction "2_2") (pintype "passive"))
      (node (ref "RC71") (pin "1") (pinfunction "1_1") (pintype "passive"))
      (node (ref "TP10") (pin "1") (pinfunction "1_1") (pintype "passive"))
      (node (ref "UC624") (pin "7") (pintype "passive"))
    )
    (net (code "19") (name "/Ipv2") (class "Default")
      (node (ref "CC448") (pin "1") (pinfunction "1_1") (pintype "passive"))
      (node (ref "UC634") (pin "13") (pintype "passive"))
      (node (ref "UC634") (pin "14") (pintype "passive"))
    )
    (net (code "20") (name "/Ipv2-P") (class "Default")
      (node (ref "CC44") (pin "2") (pinfunction "2_2") (pintype "passive"))
      (node (ref "RC79") (pin "2") (pinfunction "2_2") (pintype "passive"))
      (node (ref "RC88") (pin "1") (pinfunction "1_1") (pintype "passive"))
      (node (ref "TP12") (pin "1") (pinfunction "1_1") (pintype "passive"))
      (node (ref "UC624") (pin "1") (pintype "passive"))
    )
    (net (code "21") (name "/LOCK") (class "Default")
      (node (ref "CC48") (pin "1") (pinfunction "1_1") (pintype "passive"))
      (node (ref "RC535") (pin "2") (pinfunction "2_2") (pintype "passive"))
      (node (ref "UC50") (pin "10") (pintype "input"))
    )
    (net (code "22") (name "/M-SEL_A") (class "Default")
      (node (ref "RC172") (pin "2") (pinfunction "2_2") (pintype "passive"))
    )
    (net (code "23") (name "/M-SEL_B") (class "Default")
      (node (ref "RC176") (pin "2") (pinfunction "2_2") (pintype "passive"))
    )
    (net (code "24") (name "/M.DCI-R") (class "Default")
      (node (ref "RC52") (pin "1") (pinfunction "1_1") (pintype "passive"))
      (node (ref "UC14") (pin "12") (pinfunction "12_12") (pintype "passive"))
    )
    (net (code "25") (name "/M.DCI-R{slash}S{slash}T") (class "Default")
      (node (ref "RC166") (pin "2") (pinfunction "2_2") (pintype "passive"))
    )
    (net (code "26") (name "/M.DCI-S") (class "Default")
      (node (ref "RC127") (pin "1") (pinfunction "1_1") (pintype "passive"))
      (node (ref "UC14") (pin "14") (pinfunction "14_14") (pintype "passive"))
    )
    (net (code "27") (name "/M.DCI-T") (class "Default")
      (node (ref "RC50") (pin "1") (pinfunction "1_1") (pintype "passive"))
      (node (ref "UC14") (pin "15") (pinfunction "15_15") (pintype "passive"))
    )
    (net (code "28") (name "/M.GFCI") (class "Default")
      (node (ref "RC171") (pin "2") (pinfunction "2_2") (pintype "passive"))
      (node (ref "TP20") (pin "1") (pinfunction "1_1") (pintype "passive"))
    )
    (net (code "29") (name "/M.VgridR") (class "Default")
      (node (ref "RC14") (pin "2") (pinfunction "2_2") (pintype "passive"))
    )
    (net (code "30") (name "/M.VgridS") (class "Default")
      (node (ref "RC72") (pin "2") (pinfunction "2_2") (pintype "passive"))
    )
    (net (code "31") (name "/M.VgridT") (class "Default")
      (node (ref "RC128") (pin "2") (pinfunction "2_2") (pintype "passive"))
    )
    (net (code "32") (name "/M.Vpv1") (class "Default")
      (node (ref "RC4") (pin "2") (pinfunction "2_2") (pintype "passive"))
    )
    (net (code "33") (name "/M.Vpv2") (class "Default")
      (node (ref "RC33") (pin "2") (pinfunction "2_2") (pintype "passive"))
    )
    (net (code "34") (name "/OUTOCP1") (class "Default") (node (ref "UC50") (pin "8") (pintype "output")))
    (net (code "35") (name "/RESET-IN") (class "Default")
      (node (ref "CC47") (pin "2") (pinfunction "2_2") (pintype "passive"))
      (node (ref "RC534") (pin "2") (pinfunction "2_2") (pintype "passive"))
      (node (ref "UC50") (pin "2") (pintype "input"))
    )
    (net (code "36") (name "/S-SEL_C") (class "Default")
      (node (ref "RC196") (pin "2") (pinfunction "2_2") (pintype "passive"))
    )
    (net (code "37") (name "/S-SEL_D") (class "Default")
      (node (ref "RC197") (pin "2") (pinfunction "2_2") (pintype "passive"))
    )
    (net (code "38") (name "/S.DCI-R") (class "Default")
      (node (ref "RC56") (pin "1") (pinfunction "1_1") (pintype "passive"))
    )
    (net (code "39") (name "/S.DCI-S") (class "Default")
      (node (ref "RC137") (pin "1") (pinfunction "1_1") (pintype "passive"))
    )
    (net (code "40") (name "/S.DCI-T") (class "Default")
      (node (ref "RC55") (pin "1") (pinfunction "1_1") (pintype "passive"))
    )
    (net (code "41") (name "/S.GFCI") (class "Default")
      (node (ref "RC175") (pin "2") (pinfunction "2_2") (pintype "passive"))
    )
    (net (code "42") (name "/S.Temp-Boost{slash}Amb") (class "Default")
      (node (ref "RC187") (pin "1") (pinfunction "1_1") (pintype "passive"))
    )
    (net (code "43") (name "/S.Temp-INV") (class "Default")
      (node (ref "RC189") (pin "2") (pinfunction "2_2") (pintype "passive"))
    )
    (net (code "44") (name "/S.V-INV-R") (class "Default")
      (node (ref "RC168") (pin "2") (pinfunction "2_2") (pintype "passive"))
      (node (ref "RC169") (pin "1") (pinfunction "1_1") (pintype "passive"))
    )
    (net (code "45") (name "/S.V-INV-S") (class "Default")
      (node (ref "RC181") (pin "2") (pinfunction "2_2") (pintype "passive"))
      (node (ref "RC184") (pin "1") (pinfunction "1_1") (pintype "passive"))
    )
    (net (code "46") (name "/S.V-INV-T") (class "Default")
      (node (ref "RC200") (pin "2") (pinfunction "2_2") (pintype "passive"))
      (node (ref "RC201") (pin "1") (pinfunction "1_1") (pintype "passive"))
    )
    (net (code "47") (name "/S.VgridR") (class "Default")
      (node (ref "RC3") (pin "2") (pinfunction "2_2") (pintype "passive"))
    )
    (net (code "48") (name "/S.VgridS") (class "Default")
      (node (ref "RC65") (pin "2") (pinfunction "2_2") (pintype "passive"))
    )
    (net (code "49") (name "/S.VgridT") (class "Default")
      (node (ref "RC111") (pin "2") (pinfunction "2_2") (pintype "passive"))
    )
    (net (code "50") (name "/S.Viso-PV1") (class "Default")
      (node (ref "RC183") (pin "2") (pinfunction "2_2") (pintype "passive"))
      (node (ref "TP24") (pin "1") (pinfunction "1_1") (pintype "passive"))
    )
    (net (code "51") (name "/S.Vpv1") (class "Default")
      (node (ref "RC11") (pin "2") (pinfunction "2_2") (pintype "passive"))
    )
    (net (code "52") (name "/S.Vpv2") (class "Default")
      (node (ref "RC39") (pin "2") (pinfunction "2_2") (pintype "passive"))
    )
    (net (code "53") (name "/TempAmb") (class "Default")
      (node (ref "UC16") (pin "12") (pinfunction "12_12") (pintype "passive"))
    )
    (net (code "54") (name "/TempBoost1") (class "Default")
      (node (ref "UC16") (pin "15") (pinfunction "15_15") (pintype "passive"))
    )
    (net (code "55") (name "/TempBoost2") (class "Default")
      (node (ref "UC16") (pin "14") (pinfunction "14_14") (pintype "passive"))
    )
    (net (code "56") (name "/TempINVR") (class "Default")
      (node (ref "UC16") (pin "1") (pinfunction "1_1") (pintype "passive"))
    )
    (net (code "57") (name "/TempINVS") (class "Default")
      (node (ref "UC16") (pin "2") (pinfunction "2_2") (pintype "passive"))
    )
    (net (code "58") (name "/TempINVT") (class "Default")
      (node (ref "UC16") (pin "5") (pinfunction "5_5") (pintype "passive"))
    )
    (net (code "59") (name "/VBus+") (class "Default")
      (node (ref "RC104") (pin "1") (pinfunction "1_1") (pintype "passive"))
    )
    (net (code "60") (name "/VBus-") (class "Default")
      (node (ref "RC151") (pin "1") (pinfunction "1_1") (pintype "passive"))
    )
    (net (code "61") (name "/VBus01") (class "Default")
      (node (ref "RC118") (pin "1") (pinfunction "1_1") (pintype "passive"))
    )
    (net (code "62") (name "/VBus02") (class "Default")
      (node (ref "RC145") (pin "1") (pinfunction "1_1") (pintype "passive"))
    )
    (net (code "63") (name "/VBusN") (class "Default")
      (node (ref "RC146") (pin "1") (pinfunction "1_1") (pintype "passive"))
    )
    (net (code "64") (name "/VBusP") (class "Default")
      (node (ref "RC105") (pin "1") (pinfunction "1_1") (pintype "passive"))
    )
    (net (code "65") (name "/VgridR+") (class "Default")
      (node (ref "RC6") (pin "2") (pinfunction "2_2") (pintype "passive"))
    )
    (net (code "66") (name "/VgridR-") (class "Default")
      (node (ref "RC19") (pin "1") (pinfunction "1_1") (pintype "passive"))
    )
    (net (code "67") (name "/VgridS+") (class "Default")
      (node (ref "RC67") (pin "2") (pinfunction "2_2") (pintype "passive"))
    )
    (net (code "68") (name "/VgridS-") (class "Default")
      (node (ref "RC73") (pin "1") (pinfunction "1_1") (pintype "passive"))
    )
    (net (code "69") (name "/VgridT+") (class "Default")
      (node (ref "RC116") (pin "2") (pinfunction "2_2") (pintype "passive"))
    )
    (net (code "70") (name "/VgridT-") (class "Default")
      (node (ref "RC132") (pin "1") (pinfunction "1_1") (pintype "passive"))
    )
    (net (code "71") (name "/VinvR+") (class "Default")
      (node (ref "RC167") (pin "1") (pinfunction "1_1") (pintype "passive"))
    )
    (net (code "72") (name "/VinvR-") (class "Default")
      (node (ref "RC177") (pin "1") (pinfunction "1_1") (pintype "passive"))
    )
    (net (code "73") (name "/VinvS+") (class "Default")
      (node (ref "RC180") (pin "1") (pinfunction "1_1") (pintype "passive"))
    )
    (net (code "74") (name "/VinvS-") (class "Default")
      (node (ref "RC191") (pin "1") (pinfunction "1_1") (pintype "passive"))
    )
    (net (code "75") (name "/VinvT+") (class "Default")
      (node (ref "RC199") (pin "1") (pinfunction "1_1") (pintype "passive"))
    )
    (net (code "76") (name "/VinvT-") (class "Default")
      (node (ref "RC202") (pin "1") (pinfunction "1_1") (pintype "passive"))
    )
    (net (code "77") (name "1.5VREF") (class "Default")
      (node (ref "CC10") (pin "2") (pinfunction "2_2") (pintype "passive"))
      (node (ref "CC14") (pin "2") (pinfunction "2_2") (pintype "passive"))
      (node (ref "CC36") (pin "2") (pinfunction "2_2") (pintype "passive"))
      (node (ref "CC37") (pin "2") (pinfunction "2_2") (pintype "passive"))
      (node (ref "CC53") (pin "2") (pinfunction "2_2") (pintype "passive"))
      (node (ref "CC69") (pin "2") (pinfunction "2_2") (pintype "passive"))
      (node (ref "CC79") (pin "1") (pinfunction "1_1") (pintype "passive"))
      (node (ref "RC100") (pin "2") (pinfunction "2_2") (pintype "passive"))
      (node (ref "RC140") (pin "1") (pinfunction "1_1") (pintype "passive"))
      (node (ref "RC158") (pin "2") (pinfunction "2_2") (pintype "passive"))
      (node (ref "RC25") (pin "2") (pinfunction "2_2") (pintype "passive"))
      (node (ref "RC29") (pin "2") (pinfunction "2_2") (pintype "passive"))
      (node (ref "RC61") (pin "1") (pinfunction "1_1") (pintype "passive"))
      (node (ref "RC64") (pin "1") (pinfunction "1_1") (pintype "passive"))
      (node (ref "UC12") (pin "2") (pinfunction "Vout_2") (pintype "passive"))
    )
    (net (code "78") (name "3") (class "Default")
      (node (ref "UC636") (pin "3") (pinfunction "3_3") (pintype "power_in"))
    )
    (net (code "79") (name "12") (class "Default")
      (node (ref "UC636") (pin "12") (pinfunction "12_12") (pintype "power_in"))
    )
    (net (code "80") (name "DSP_OUTOCP") (class "Default")
      (node (ref "UC50") (pin "3") (pintype "output"))
      (node (ref "UC50") (pin "5") (pintype "input"))
      (node (ref "UC50") (pin "9") (pintype "input"))
    )
    (net (code "81") (name "EARTH") (class "Default")
      (node (ref "RC195") (pin "2") (pinfunction "2_2") (pintype "passive"))
      (node (ref "SC6") (pin "1") (pinfunction "1_1") (pintype "passive"))
    )
    (net (code "82") (name "GND") (class "Default")
      (node (ref "CC1") (pin "1") (pinfunction "1_1") (pintype "passive"))
      (node (ref "CC100") (pin "1") (pinfunction "1_1") (pintype "passive"))
      (node (ref "CC101") (pin "1") (pinfunction "1_1") (pintype "passive"))
      (node (ref "CC12") (pin "2") (pinfunction "2_2") (pintype "passive"))
      (node (ref "CC15") (pin "2") (pinfunction "2_2") (pintype "passive"))
      (node (ref "CC16") (pin "2") (pinfunction "2_2") (pintype "passive"))
      (node (ref "CC17") (pin "2") (pinfunction "2_2") (pintype "passive"))
      (node (ref "CC177") (pin "2") (pinfunction "2_2") (pintype "passive"))
      (node (ref "CC178") (pin "2") (pinfunction "2_2") (pintype "passive"))
      (node (ref "CC18") (pin "2") (pinfunction "2_2") (pintype "passive"))
      (node (ref "CC19") (pin "1") (pinfunction "1_1") (pintype "passive"))
      (node (ref "CC2") (pin "1") (pinfunction "1_1") (pintype "passive"))
      (node (ref "CC20") (pin "2") (pinfunction "2_2") (pintype "passive"))
      (node (ref "CC21") (pin "2") (pinfunction "2_2") (pintype "passive"))
      (node (ref "CC216") (pin "1") (pinfunction "1_1") (pintype "passive"))
      (node (ref "CC23") (pin "2") (pinfunction "2_2") (pintype "passive"))
      (node (ref "CC277") (pin "2") (pinfunction "2_2") (pintype "passive"))
      (node (ref "CC280") (pin "2") (pinfunction "2_2") (pintype "passive"))
      (node (ref "CC31") (pin "2") (pinfunction "2_2") (pintype "passive"))
      (node (ref "CC34") (pin "2") (pinfunction "2_2") (pintype "passive"))
      (node (ref "CC35") (pin "2") (pinfunction "2_2") (pintype "passive"))
      (node (ref "CC38") (pin "1") (pinfunction "1_1") (pintype "passive"))
      (node (ref "CC40") (pin "2") (pinfunction "2_2") (pintype "passive"))
      (node (ref "CC447") (pin "2") (pinfunction "2_2") (pintype "passive"))
      (node (ref "CC449") (pin "2") (pinfunction "2_2") (pintype "passive"))
      (node (ref "CC45") (pin "1") (pinfunction "1_1") (pintype "passive"))
      (node (ref "CC46") (pin "2") (pinfunction "2_2") (pintype "passive"))
      (node (ref "CC47") (pin "1") (pinfunction "1_1") (pintype "passive"))
      (node (ref "CC48") (pin "2") (pinfunction "2_2") (pintype "passive"))
      (node (ref "CC49") (pin "1") (pinfunction "1_1") (pintype "passive"))
      (node (ref "CC54") (pin "2") (pinfunction "2_2") (pintype "passive"))
      (node (ref "CC55") (pin "1") (pinfunction "1_1") (pintype "passive"))
      (node (ref "CC57") (pin "1") (pinfunction "1_1") (pintype "passive"))
      (node (ref "CC58") (pin "1") (pinfunction "1_1") (pintype "passive"))
      (node (ref "CC59") (pin "1") (pinfunction "1_1") (pintype "passive"))
      (node (ref "CC62") (pin "2") (pinfunction "2_2") (pintype "passive"))
      (node (ref "CC63") (pin "2") (pinfunction "2_2") (pintype "passive"))
      (node (ref "CC64") (pin "1") (pinfunction "1_1") (pintype "passive"))
      (node (ref "CC65") (pin "1") (pinfunction "1_1") (pintype "passive"))
      (node (ref "CC67") (pin "1") (pinfunction "1_1") (pintype "passive"))
      (node (ref "CC68") (pin "2") (pinfunction "2_2") (pintype "passive"))
      (node (ref "CC7") (pin "1") (pinfunction "1_1") (pintype "passive"))
      (node (ref "CC70") (pin "2") (pinfunction "2_2") (pintype "passive"))
      (node (ref "CC71") (pin "2") (pinfunction "2_2") (pintype "passive"))
      (node (ref "CC72") (pin "1") (pinfunction "1_1") (pintype "passive"))
      (node (ref "CC73") (pin "1") (pinfunction "1_1") (pintype "passive"))
      (node (ref "CC76") (pin "2") (pinfunction "2_2") (pintype "passive"))
      (node (ref "CC77") (pin "2") (pinfunction "2_2") (pintype "passive"))
      (node (ref "CC78") (pin "1") (pinfunction "1_1") (pintype "passive"))
      (node (ref "CC79") (pin "2") (pinfunction "2_2") (pintype "passive"))
      (node (ref "CC8") (pin "2") (pinfunction "2_2") (pintype "passive"))
      (node (ref "CC80") (pin "2") (pinfunction "2_2") (pintype "passive"))
      (node (ref "CC82") (pin "2") (pinfunction "2_2") (pintype "passive"))
      (node (ref "CC84") (pin "1") (pinfunction "1_1") (pintype "passive"))
      (node (ref "CC85") (pin "1") (pinfunction "1_1") (pintype "passive"))
      (node (ref "CC86") (pin "1") (pinfunction "1_1") (pintype "passive"))
      (node (ref "CC87") (pin "2") (pinfunction "2_2") (pintype "passive"))
      (node (ref "CC88") (pin "2") (pinfunction "2_2") (pintype "passive"))
      (node (ref "CC9") (pin "2") (pinfunction "2_2") (pintype "passive"))
      (node (ref "CC90") (pin "1") (pinfunction "1_1") (pintype "passive"))
      (node (ref "CC92") (pin "1") (pinfunction "1_1") (pintype "passive"))
      (node (ref "CC93") (pin "1") (pinfunction "1_1") (pintype "passive"))
      (node (ref "CC94") (pin "1") (pinfunction "1_1") (pintype "passive"))
      (node (ref "CC95") (pin "1") (pinfunction "1_1") (pintype "passive"))
      (node (ref "CC96") (pin "1") (pinfunction "1_1") (pintype "passive"))
      (node (ref "CC98") (pin "1") (pinfunction "1_1") (pintype "passive"))
      (node (ref "CC99") (pin "1") (pinfunction "1_1") (pintype "passive"))
      (node (ref "RC1") (pin "1") (pinfunction "1_1") (pintype "passive"))
      (node (ref "RC101") (pin "2") (pinfunction "2_2") (pintype "passive"))
      (node (ref "RC103") (pin "2") (pinfunction "2_2") (pintype "passive"))
      (node (ref "RC108") (pin "1") (pinfunction "1_1") (pintype "passive"))
      (node (ref "RC113") (pin "2") (pinfunction "2_2") (pintype "passive"))
      (node (ref "RC124") (pin "2") (pinfunction "2_2") (pintype "passive"))
      (node (ref "RC13") (pin "1") (pinfunction "1_1") (pintype "passive"))
      (node (ref "RC133") (pin "1") (pinfunction "1_1") (pintype "passive"))
      (node (ref "RC142") (pin "2") (pinfunction "2_2") (pintype "passive"))
      (node (ref "RC144") (pin "2") (pinfunction "2_2") (pintype "passive"))
      (node (ref "RC150") (pin "1") (pinfunction "1_1") (pintype "passive"))
      (node (ref "RC157") (pin "2") (pinfunction "2_2") (pintype "passive"))
      (node (ref "RC158") (pin "1") (pinfunction "1_1") (pintype "passive"))
      (node (ref "RC161") (pin "2") (pinfunction "2_2") (pintype "passive"))
      (node (ref "RC162") (pin "1") (pinfunction "0_1") (pintype "passive"))
      (node (ref "RC162") (pin "2") (pinfunction "1_2") (pintype "passive"))
      (node (ref "RC162") (pin "3") (pinfunction "2_3") (pintype "passive"))
      (node (ref "RC162") (pin "4") (pinfunction "3_4") (pintype "passive"))
      (node (ref "RC165") (pin "1") (pinfunction "1_1") (pintype "passive"))
      (node (ref "RC170") (pin "1") (pinfunction "1_1") (pintype "passive"))
      (node (ref "RC173") (pin "2") (pinfunction "2_2") (pintype "passive"))
      (node (ref "RC179") (pin "1") (pinfunction "1_1") (pintype "passive"))
      (node (ref "RC188") (pin "1") (pinfunction "1_1") (pintype "passive"))
      (node (ref "RC193") (pin "2") (pinfunction "2_2") (pintype "passive"))
      (node (ref "RC194") (pin "2") (pinfunction "2_2") (pintype "passive"))
      (node (ref "RC198") (pin "1") (pinfunction "1_1") (pintype "passive"))
      (node (ref "RC26") (pin "2") (pinfunction "2_2") (pintype "passive"))
      (node (ref "RC30") (pin "2") (pinfunction "2_2") (pintype "passive"))
      (node (ref "RC31") (pin "2") (pinfunction "2_2") (pintype "passive"))
      (node (ref "RC38") (pin "1") (pinfunction "1_1") (pintype "passive"))
      (node (ref "RC41") (pin "1") (pinfunction "1_1") (pintype "passive"))
      (node (ref "RC43") (pin "1") (pinfunction "1_1") (pintype "passive"))
      (node (ref "RC5") (pin "2") (pinfunction "2_2") (pintype "passive"))
      (node (ref "RC533") (pin "1") (pinfunction "1_1") (pintype "passive"))
      (node (ref "RC534") (pin "1") (pinfunction "1_1") (pintype "passive"))
      (node (ref "RC535") (pin "1") (pinfunction "1_1") (pintype "passive"))
      (node (ref "RC54") (pin "2") (pinfunction "2_2") (pintype "passive"))
      (node (ref "RC66") (pin "2") (pinfunction "2_2") (pintype "passive"))
      (node (ref "RC706") (pin "2") (pinfunction "2_2") (pintype "passive"))
      (node (ref "RC74") (pin "2") (pinfunction "2_2") (pintype "passive"))
      (node (ref "RC83") (pin "1") (pinfunction "1_1") (pintype "passive"))
      (node (ref "RC9") (pin "1") (pinfunction "1_1") (pintype "passive"))
      (node (ref "UC12") (pin "1") (pinfunction "ADJ_1") (pintype "passive"))
      (node (ref "UC14") (pin "6") (pinfunction "6_6") (pintype "passive"))
      (node (ref "UC14") (pin "7") (pinfunction "7_7") (pintype "passive"))
      (node (ref "UC14") (pin "8") (pinfunction "8_8") (pintype "power_in"))
      (node (ref "UC16") (pin "6") (pinfunction "6_6") (pintype "passive"))
      (node (ref "UC16") (pin "7") (pinfunction "7_7") (pintype "passive"))
      (node (ref "UC16") (pin "8") (pinfunction "8_8") (pintype "power_in"))
      (node (ref "UC50") (pin "12") (pintype "input"))
      (node (ref "UC50") (pin "13") (pintype "input"))
      (node (ref "UC50") (pin "7") (pinfunction "GND_7") (pintype "passive"))
      (node (ref "UC626") (pin "4") (pinfunction "4_4") (pintype "power_in"))
      (node (ref "UC634") (pin "10") (pintype "passive"))
      (node (ref "UC636") (pin "10") (pintype "passive"))
      (node (ref "UC636") (pin "11") (pintype "passive"))
      (node (ref "UC636") (pin "12") (pinfunction "12_12") (pintype "passive"))
      (node (ref "UC636") (pin "4") (pintype "passive"))
      (node (ref "UC636") (pin "5") (pintype "passive"))
    )
    (net (code "83") (name "Ipv1+") (class "Default")
      (node (ref "RC57") (pin "2") (pinfunction "2_2") (pintype "passive"))
    )
    (net (code "84") (name "Ipv1-") (class "Default")
      (node (ref "RC69") (pin "2") (pinfunction "2_2") (pintype "passive"))
    )
    (net (code "85") (name "Ipv2+") (class "Default")
      (node (ref "RC76") (pin "2") (pinfunction "2_2") (pintype "passive"))
    )
    (net (code "86") (name "Ipv2-") (class "Default")
      (node (ref "RC87") (pin "2") (pinfunction "2_2") (pintype "passive"))
    )
    (net (code "87") (name "Net-(CC1-Pad2)") (class "Default")
      (node (ref "CC1") (pin "2") (pinfunction "2_2") (pintype "passive"))
      (node (ref "RC1") (pin "2") (pinfunction "2_2") (pintype "passive"))
      (node (ref "RC2") (pin "1") (pinfunction "1_1") (pintype "passive"))
      (node (ref "UC624") (pin "12") (pintype "passive"))
    )
    (net (code "88") (name "Net-(CC2-Pad2)") (class "Default")
      (node (ref "CC2") (pin "2") (pinfunction "2_2") (pintype "passive"))
      (node (ref "RC5") (pin "1") (pinfunction "1_1") (pintype "passive"))
      (node (ref "RC6") (pin "1") (pinfunction "1_1") (pintype "passive"))
      (node (ref "UC627") (pin "3") (pintype "passive"))
    )
    (net (code "89") (name "Net-(CC3-Pad1)") (class "Default")
      (node (ref "CC3") (pin "1") (pinfunction "1_1") (pintype "passive"))
      (node (ref "RC10") (pin "1") (pinfunction "1_1") (pintype "passive"))
      (node (ref "RC16") (pin "2") (pinfunction "2_2") (pintype "passive"))
      (node (ref "TP3") (pin "1") (pinfunction "1_1") (pintype "passive"))
      (node (ref "UC635") (pin "1") (pintype "passive"))
    )
    (net (code "90") (name "Net-(CC3-Pad2)") (class "Default")
      (node (ref "CC3") (pin "2") (pinfunction "2_2") (pintype "passive"))
      (node (ref "RC10") (pin "2") (pinfunction "2_2") (pintype "passive"))
      (node (ref "RC9") (pin "2") (pinfunction "2_2") (pintype "passive"))
      (node (ref "UC635") (pin "2") (pintype "passive"))
    )
    (net (code "91") (name "Net-(CC4-Pad1)") (class "Default")
      (node (ref "CC4") (pin "1") (pinfunction "1_1") (pintype "passive"))
      (node (ref "RC12") (pin "1") (pinfunction "1_1") (pintype "passive"))
      (node (ref "RC18") (pin "2") (pinfunction "2_2") (pintype "passive"))
      (node (ref "TP4") (pin "1") (pinfunction "1_1") (pintype "passive"))
      (node (ref "UC632") (pin "1") (pintype "passive"))
    )
    (net (code "92") (name "Net-(CC4-Pad2)") (class "Default")
      (node (ref "CC4") (pin "2") (pinfunction "2_2") (pintype "passive"))
      (node (ref "RC12") (pin "2") (pinfunction "2_2") (pintype "passive"))
      (node (ref "RC13") (pin "2") (pinfunction "2_2") (pintype "passive"))
      (node (ref "UC632") (pin "2") (pintype "passive"))
    )
    (net (code "93") (name "Net-(CC5-Pad1)") (class "Default")
      (node (ref "CC5") (pin "1") (pinfunction "1_1") (pintype "passive"))
      (node (ref "RC11") (pin "1") (pinfunction "1_1") (pintype "passive"))
      (node (ref "RC20") (pin "1") (pinfunction "1_1") (pintype "passive"))
      (node (ref "RC4") (pin "1") (pinfunction "1_1") (pintype "passive"))
      (node (ref "TP2") (pin "1") (pinfunction "1_1") (pintype "passive"))
      (node (ref "UC624") (pin "14") (pintype "passive"))
    )
    (net (code "94") (name "Net-(CC5-Pad2)") (class "Default")
      (node (ref "CC5") (pin "2") (pinfunction "2_2") (pintype "passive"))
      (node (ref "RC15") (pin "1") (pinfunction "1_1") (pintype "passive"))
      (node (ref "RC20") (pin "2") (pinfunction "2_2") (pintype "passive"))
      (node (ref "UC624") (pin "13") (pintype "passive"))
    )
    (net (code "95") (name "Net-(CC6-Pad1)") (class "Default")
      (node (ref "CC6") (pin "1") (pinfunction "1_1") (pintype "passive"))
      (node (ref "RC21") (pin "2") (pinfunction "2_2") (pintype "passive"))
      (node (ref "RC8") (pin "2") (pinfunction "2_2") (pintype "passive"))
      (node (ref "UC627") (pin "1") (pintype "passive"))
    )
    (net (code "96") (name "Net-(CC6-Pad2)") (class "Default")
      (node (ref "CC6") (pin "2") (pinfunction "2_2") (pintype "passive"))
      (node (ref "RC19") (pin "2") (pinfunction "2_2") (pintype "passive"))
      (node (ref "RC21") (pin "1") (pinfunction "1_1") (pintype "passive"))
      (node (ref "UC627") (pin "2") (pintype "passive"))
    )
    (net (code "97") (name "Net-(CC7-Pad2)") (class "Default")
      (node (ref "CC7") (pin "2") (pinfunction "2_2") (pintype "passive"))
      (node (ref "RC30") (pin "1") (pinfunction "1_1") (pintype "passive"))
      (node (ref "RC32") (pin "1") (pinfunction "1_1") (pintype "passive"))
      (node (ref "UC624") (pin "10") (pintype "passive"))
    )
    (net (code "98") (name "Net-(CC10-Pad1)") (class "Default")
      (node (ref "CC10") (pin "1") (pinfunction "1_1") (pintype "passive"))
      (node (ref "RC17") (pin "2") (pinfunction "2_2") (pintype "passive"))
      (node (ref "RC25") (pin "1") (pinfunction "1_1") (pintype "passive"))
      (node (ref "UC635") (pin "3") (pintype "passive"))
    )
    (net (code "99") (name "Net-(CC11-Pad1)") (class "Default")
      (node (ref "CC11") (pin "1") (pinfunction "1_1") (pintype "passive"))
      (node (ref "DC1") (pin "3") (pinfunction "3_3") (pintype "passive"))
      (node (ref "RC17") (pin "1") (pinfunction "1_1") (pintype "passive"))
      (node (ref "RC35") (pin "1") (pinfunction "1_1") (pintype "passive"))
      (node (ref "RC58") (pin "2") (pinfunction "2_2") (pintype "passive"))
      (node (ref "UC635") (pin "7") (pintype "passive"))
    )
    (net (code "100") (name "Net-(CC11-Pad2)") (class "Default")
      (node (ref "CC11") (pin "2") (pinfunction "2_2") (pintype "passive"))
      (node (ref "RC34") (pin "1") (pinfunction "1_1") (pintype "passive"))
      (node (ref "RC35") (pin "2") (pinfunction "2_2") (pintype "passive"))
      (node (ref "UC635") (pin "6") (pintype "passive"))
    )
    (net (code "101") (name "Net-(CC12-Pad1)") (class "Default")
      (node (ref "CC12") (pin "1") (pinfunction "1_1") (pintype "passive"))
      (node (ref "RC23") (pin "1") (pinfunction "1_1") (pintype "passive"))
      (node (ref "RC26") (pin "1") (pinfunction "1_1") (pintype "passive"))
      (node (ref "UC635") (pin "5") (pintype "passive"))
    )
    (net (code "102") (name "Net-(CC13-Pad1)") (class "Default")
      (node (ref "CC13") (pin "1") (pinfunction "1_1") (pintype "passive"))
      (node (ref "DC2") (pin "3") (pinfunction "3_3") (pintype "passive"))
      (node (ref "RC22") (pin "1") (pinfunction "1_1") (pintype "passive"))
      (node (ref "RC37") (pin "1") (pinfunction "1_1") (pintype "passive"))
      (node (ref "RC62") (pin "2") (pinfunction "2_2") (pintype "passive"))
      (node (ref "UC632") (pin "7") (pintype "passive"))
    )
    (net (code "103") (name "Net-(CC13-Pad2)") (class "Default")
      (node (ref "CC13") (pin "2") (pinfunction "2_2") (pintype "passive"))
      (node (ref "RC37") (pin "2") (pinfunction "2_2") (pintype "passive"))
      (node (ref "RC42") (pin "1") (pinfunction "1_1") (pintype "passive"))
      (node (ref "UC632") (pin "6") (pintype "passive"))
    )
    (net (code "104") (name "Net-(CC14-Pad1)") (class "Default")
      (node (ref "CC14") (pin "1") (pinfunction "1_1") (pintype "passive"))
      (node (ref "RC22") (pin "2") (pinfunction "2_2") (pintype "passive"))
      (node (ref "RC29") (pin "1") (pinfunction "1_1") (pintype "passive"))
      (node (ref "UC632") (pin "3") (pintype "passive"))
    )
    (net (code "105") (name "Net-(CC23-Pad1)") (class "Default")
      (node (ref "CC23") (pin "1") (pinfunction "1_1") (pintype "passive"))
      (node (ref "RC24") (pin "1") (pinfunction "1_1") (pintype "passive"))
      (node (ref "RC31") (pin "1") (pinfunction "1_1") (pintype "passive"))
      (node (ref "UC632") (pin "5") (pintype "passive"))
    )
    (net (code "106") (name "Net-(CC24-Pad1)") (class "Default")
      (node (ref "CC24") (pin "1") (pinfunction "1_1") (pintype "passive"))
      (node (ref "RC45") (pin "2") (pinfunction "2_2") (pintype "passive"))
      (node (ref "RC50") (pin "2") (pinfunction "2_2") (pintype "passive"))
      (node (ref "RC55") (pin "2") (pinfunction "2_2") (pintype "passive"))
      (node (ref "TP8") (pin "1") (pinfunction "1_1") (pintype "passive"))
      (node (ref "UC635") (pin "14") (pintype "passive"))
    )
    (net (code "107") (name "Net-(CC24-Pad2)") (class "Default")
      (node (ref "CC24") (pin "2") (pinfunction "2_2") (pintype "passive"))
      (node (ref "RC38") (pin "2") (pinfunction "2_2") (pintype "passive"))
      (node (ref "RC45") (pin "1") (pinfunction "1_1") (pintype "passive"))
      (node (ref "UC635") (pin "13") (pintype "passive"))
    )
    (net (code "108") (name "Net-(CC26-Pad1)") (class "Default")
      (node (ref "CC26") (pin "1") (pinfunction "1_1") (pintype "passive"))
      (node (ref "RC41") (pin "2") (pinfunction "2_2") (pintype "passive"))
      (node (ref "RC44") (pin "1") (pinfunction "1_1") (pintype "passive"))
      (node (ref "UC632") (pin "13") (pintype "passive"))
    )
    (net (code "109") (name "Net-(CC26-Pad2)") (class "Default")
      (node (ref "CC26") (pin "2") (pinfunction "2_2") (pintype "passive"))
      (node (ref "RC44") (pin "2") (pinfunction "2_2") (pintype "passive"))
      (node (ref "RC52") (pin "2") (pinfunction "2_2") (pintype "passive"))
      (node (ref "RC56") (pin "2") (pinfunction "2_2") (pintype "passive"))
      (node (ref "TP9") (pin "1") (pinfunction "1_1") (pintype "passive"))
      (node (ref "UC632") (pin "14") (pintype "passive"))
    )
    (net (code "110") (name "Net-(CC27-Pad1)") (class "Default")
      (node (ref "CC27") (pin "1") (pinfunction "1_1") (pintype "passive"))
      (node (ref "RC33") (pin "1") (pinfunction "1_1") (pintype "passive"))
      (node (ref "RC39") (pin "1") (pinfunction "1_1") (pintype "passive"))
      (node (ref "RC48") (pin "1") (pinfunction "1_1") (pintype "passive"))
      (node (ref "TP5") (pin "1") (pinfunction "1_1") (pintype "passive"))
      (node (ref "UC624") (pin "8") (pintype "passive"))
    )
    (net (code "111") (name "Net-(CC27-Pad2)") (class "Default")
      (node (ref "CC27") (pin "2") (pinfunction "2_2") (pintype "passive"))
      (node (ref "RC46") (pin "1") (pinfunction "1_1") (pintype "passive"))
      (node (ref "RC48") (pin "2") (pinfunction "2_2") (pintype "passive"))
      (node (ref "UC624") (pin "9") (pintype "passive"))
    )
    (net (code "112") (name "Net-(CC31-Pad1)") (class "Default")
      (node (ref "CC31") (pin "1") (pinfunction "1_1") (pintype "passive"))
      (node (ref "RC54") (pin "1") (pinfunction "1_1") (pintype "passive"))
      (node (ref "RC57") (pin "1") (pinfunction "1_1") (pintype "passive"))
      (node (ref "UC624") (pin "5") (pintype "passive"))
    )
    (net (code "113") (name "Net-(CC32-Pad1)") (class "Default")
      (node (ref "CC32") (pin "1") (pinfunction "1_1") (pintype "passive"))
      (node (ref "RC51") (pin "1") (pinfunction "1_1") (pintype "passive"))
      (node (ref "UC635") (pin "8") (pintype "passive"))
      (node (ref "UC635") (pin "9") (pintype "passive"))
    )
    (net (code "114") (name "Net-(CC32-Pad2)") (class "Default")
      (node (ref "CC32") (pin "2") (pinfunction "2_2") (pintype "passive"))
      (node (ref "RC58") (pin "1") (pinfunction "1_1") (pintype "passive"))
      (node (ref "RC59") (pin "2") (pinfunction "2_2") (pintype "passive"))
    )
    (net (code "115") (name "Net-(CC33-Pad1)") (class "Default")
      (node (ref "CC33") (pin "1") (pinfunction "1_1") (pintype "passive"))
      (node (ref "RC53") (pin "1") (pinfunction "1_1") (pintype "passive"))
      (node (ref "UC632") (pin "8") (pintype "passive"))
      (node (ref "UC632") (pin "9") (pintype "passive"))
    )
    (net (code "116") (name "Net-(CC33-Pad2)") (class "Default")
      (node (ref "CC33") (pin "2") (pinfunction "2_2") (pintype "passive"))
      (node (ref "RC62") (pin "1") (pinfunction "1_1") (pintype "passive"))
      (node (ref "RC63") (pin "2") (pinfunction "2_2") (pintype "passive"))
    )
    (net (code "117") (name "Net-(CC34-Pad1)") (class "Default")
      (node (ref "CC34") (pin "1") (pinfunction "1_1") (pintype "passive"))
      (node (ref "RC59") (pin "1") (pinfunction "1_1") (pintype "passive"))
      (node (ref "UC635") (pin "10") (pintype "passive"))
    )
    (net (code "118") (name "Net-(CC35-Pad1)") (class "Default")
      (node (ref "CC35") (pin "1") (pinfunction "1_1") (pintype "passive"))
      (node (ref "RC63") (pin "1") (pinfunction "1_1") (pintype "passive"))
      (node (ref "UC632") (pin "10") (pintype "passive"))
    )
    (net (code "119") (name "Net-(CC36-Pad1)") (class "Default")
      (node (ref "CC36") (pin "1") (pinfunction "1_1") (pintype "passive"))
      (node (ref "RC51") (pin "2") (pinfunction "2_2") (pintype "passive"))
      (node (ref "RC61") (pin "2") (pinfunction "2_2") (pintype "passive"))
      (node (ref "UC635") (pin "12") (pintype "passive"))
    )
    (net (code "120") (name "Net-(CC37-Pad1)") (class "Default")
      (node (ref "CC37") (pin "1") (pinfunction "1_1") (pintype "passive"))
      (node (ref "RC53") (pin "2") (pinfunction "2_2") (pintype "passive"))
      (node (ref "RC64") (pin "2") (pinfunction "2_2") (pintype "passive"))
      (node (ref "UC632") (pin "12") (pintype "passive"))
    )
    (net (code "121") (name "Net-(CC38-Pad2)") (class "Default")
      (node (ref "CC38") (pin "2") (pinfunction "2_2") (pintype "passive"))
      (node (ref "RC66") (pin "1") (pinfunction "1_1") (pintype "passive"))
      (node (ref "RC67") (pin "1") (pinfunction "1_1") (pintype "passive"))
      (node (ref "UC629") (pin "3") (pintype "passive"))
    )
    (net (code "122") (name "Net-(CC39-Pad2)") (class "Default")
      (node (ref "CC39") (pin "2") (pinfunction "2_2") (pintype "passive"))
      (node (ref "RC69") (pin "1") (pinfunction "1_1") (pintype "passive"))
      (node (ref "RC71") (pin "2") (pinfunction "2_2") (pintype "passive"))
      (node (ref "UC624") (pin "6") (pintype "passive"))
    )
    (net (code "123") (name "Net-(CC40-Pad1)") (class "Default")
      (node (ref "CC40") (pin "1") (pinfunction "1_1") (pintype "passive"))
      (node (ref "RC74") (pin "1") (pinfunction "1_1") (pintype "passive"))
      (node (ref "RC76") (pin "1") (pinfunction "1_1") (pintype "passive"))
      (node (ref "UC624") (pin "3") (pintype "passive"))
    )
    (net (code "124") (name "Net-(CC41-Pad1)") (class "Default")
      (node (ref "CC41") (pin "1") (pinfunction "1_1") (pintype "passive"))
      (node (ref "RC70") (pin "2") (pinfunction "2_2") (pintype "passive"))
      (node (ref "RC75") (pin "2") (pinfunction "2_2") (pintype "passive"))
      (node (ref "UC629") (pin "1") (pintype "passive"))
    )
    (net (code "125") (name "Net-(CC41-Pad2)") (class "Default")
      (node (ref "CC41") (pin "2") (pinfunction "2_2") (pintype "passive"))
      (node (ref "RC73") (pin "2") (pinfunction "2_2") (pintype "passive"))
      (node (ref "RC75") (pin "1") (pinfunction "1_1") (pintype "passive"))
      (node (ref "UC629") (pin "2") (pintype "passive"))
    )
    (net (code "126") (name "Net-(CC43-Pad1)") (class "Default")
      (node (ref "CC43") (pin "1") (pinfunction "1_1") (pintype "passive"))
      (node (ref "RC84") (pin "1") (pinfunction "1_1") (pintype "passive"))
      (node (ref "RC91") (pin "2") (pinfunction "2_2") (pintype "passive"))
      (node (ref "TP13") (pin "1") (pinfunction "1_1") (pintype "passive"))
      (node (ref "UC633") (pin "1") (pintype "passive"))
    )
    (net (code "127") (name "Net-(CC43-Pad2)") (class "Default")
      (node (ref "CC43") (pin "2") (pinfunction "2_2") (pintype "passive"))
      (node (ref "RC83") (pin "2") (pinfunction "2_2") (pintype "passive"))
      (node (ref "RC84") (pin "2") (pinfunction "2_2") (pintype "passive"))
      (node (ref "UC633") (pin "2") (pintype "passive"))
    )
    (net (code "128") (name "Net-(CC44-Pad1)") (class "Default")
      (node (ref "CC44") (pin "1") (pinfunction "1_1") (pintype "passive"))
      (node (ref "RC87") (pin "1") (pinfunction "1_1") (pintype "passive"))
      (node (ref "RC88") (pin "2") (pinfunction "2_2") (pintype "passive"))
      (node (ref "UC624") (pin "2") (pintype "passive"))
    )
    (net (code "129") (name "Net-(CC45-Pad2)") (class "Default")
      (node (ref "CC45") (pin "2") (pinfunction "2_2") (pintype "passive"))
      (node (ref "DC10") (pin "2") (pinfunction "2_2") (pintype "passive"))
      (node (ref "RC532") (pin "2") (pinfunction "2_2") (pintype "passive"))
      (node (ref "TP18") (pin "1") (pinfunction "1_1") (pintype "passive"))
      (node (ref "UC50") (pin "4") (pintype "input"))
      (node (ref "UC636") (pin "1") (pintype "passive"))
      (node (ref "UC636") (pin "14") (pintype "passive"))
    )
    (net (code "130") (name "Net-(CC52-Pad1)") (class "Default")
      (node (ref "CC52") (pin "1") (pinfunction "1_1") (pintype "passive"))
      (node (ref "DC6") (pin "3") (pinfunction "3_3") (pintype "passive"))
      (node (ref "RC107") (pin "1") (pinfunction "1_1") (pintype "passive"))
      (node (ref "RC138") (pin "2") (pinfunction "2_2") (pintype "passive"))
      (node (ref "RC94") (pin "1") (pinfunction "1_1") (pintype "passive"))
      (node (ref "UC633") (pin "7") (pintype "passive"))
    )
    (net (code "131") (name "Net-(CC52-Pad2)") (class "Default")
      (node (ref "CC52") (pin "2") (pinfunction "2_2") (pintype "passive"))
      (node (ref "RC106") (pin "1") (pinfunction "1_1") (pintype "passive"))
      (node (ref "RC107") (pin "2") (pinfunction "2_2") (pintype "passive"))
      (node (ref "UC633") (pin "6") (pintype "passive"))
    )
    (net (code "132") (name "Net-(CC53-Pad1)") (class "Default")
      (node (ref "CC53") (pin "1") (pinfunction "1_1") (pintype "passive"))
      (node (ref "RC100") (pin "1") (pinfunction "1_1") (pintype "passive"))
      (node (ref "RC94") (pin "2") (pinfunction "2_2") (pintype "passive"))
      (node (ref "UC633") (pin "3") (pintype "passive"))
    )
    (net (code "133") (name "Net-(CC54-Pad1)") (class "Default")
      (node (ref "CC54") (pin "1") (pinfunction "1_1") (pintype "passive"))
      (node (ref "RC101") (pin "1") (pinfunction "1_1") (pintype "passive"))
      (node (ref "RC99") (pin "1") (pinfunction "1_1") (pintype "passive"))
      (node (ref "UC633") (pin "5") (pintype "passive"))
    )
    (net (code "134") (name "Net-(CC56-Pad1)") (class "Default")
      (node (ref "CC56") (pin "1") (pinfunction "1_1") (pintype "passive"))
      (node (ref "RC112") (pin "2") (pinfunction "2_2") (pintype "passive"))
      (node (ref "RC127") (pin "2") (pinfunction "2_2") (pintype "passive"))
      (node (ref "RC137") (pin "2") (pinfunction "2_2") (pintype "passive"))
      (node (ref "TP19") (pin "1") (pinfunction "1_1") (pintype "passive"))
      (node (ref "UC633") (pin "14") (pintype "passive"))
    )
    (net (code "135") (name "Net-(CC56-Pad2)") (class "Default")
      (node (ref "CC56") (pin "2") (pinfunction "2_2") (pintype "passive"))
      (node (ref "RC108") (pin "2") (pinfunction "2_2") (pintype "passive"))
      (node (ref "RC112") (pin "1") (pinfunction "1_1") (pintype "passive"))
      (node (ref "UC633") (pin "13") (pintype "passive"))
    )
    (net (code "136") (name "Net-(CC57-Pad2)") (class "Default")
      (node (ref "CC57") (pin "2") (pinfunction "2_2") (pintype "passive"))
      (node (ref "RC119") (pin "2") (pinfunction "2_2") (pintype "passive"))
      (node (ref "UC636") (pin "6") (pintype "passive"))
    )
    (net (code "137") (name "Net-(CC58-Pad2)") (class "Default")
      (node (ref "CC58") (pin "2") (pinfunction "2_2") (pintype "passive"))
      (node (ref "RC109") (pin "1") (pinfunction "1_1") (pintype "passive"))
      (node (ref "UC626") (pin "2") (pinfunction "2_2") (pintype "passive"))
    )
    (net (code "138") (name "Net-(CC59-Pad2)") (class "Default")
      (node (ref "CC59") (pin "2") (pinfunction "2_2") (pintype "passive"))
      (node (ref "RC113") (pin "1") (pinfunction "1_1") (pintype "passive"))
      (node (ref "RC116") (pin "1") (pinfunction "1_1") (pintype "passive"))
      (node (ref "UC630") (pin "3") (pintype "passive"))
    )
    (net (code "139") (name "Net-(CC60-Pad2)") (class "Default")
      (node (ref "CC60") (pin "2") (pinfunction "2_2") (pintype "passive"))
      (node (ref "RC105") (pin "2") (pinfunction "2_2") (pintype "passive"))
      (node (ref "RC109") (pin "2") (pinfunction "2_2") (pintype "passive"))
      (node (ref "RC126") (pin "1") (pinfunction "1_1") (pintype "passive"))
      (node (ref "TP14") (pin "1") (pinfunction "1_1") (pintype "passive"))
      (node (ref "UC625") (pin "1") (pintype "passive"))
    )
    (net (code "140") (name "Net-(CC61-Pad1)") (class "Default")
      (node (ref "CC61") (pin "1") (pinfunction "1_1") (pintype "passive"))
      (node (ref "RC122") (pin "2") (pinfunction "2_2") (pintype "passive"))
      (node (ref "RC136") (pin "2") (pinfunction "2_2") (pintype "passive"))
      (node (ref "UC630") (pin "1") (pintype "passive"))
    )
    (net (code "141") (name "Net-(CC61-Pad2)") (class "Default")
      (node (ref "CC61") (pin "2") (pinfunction "2_2") (pintype "passive"))
      (node (ref "RC132") (pin "2") (pinfunction "2_2") (pintype "passive"))
      (node (ref "RC136") (pin "1") (pinfunction "1_1") (pintype "passive"))
      (node (ref "UC630") (pin "2") (pintype "passive"))
    )
    (net (code "142") (name "Net-(CC66-Pad1)") (class "Default")
      (node (ref "CC66") (pin "1") (pinfunction "1_1") (pintype "passive"))
      (node (ref "RC131") (pin "1") (pinfunction "1_1") (pintype "passive"))
      (node (ref "UC633") (pin "8") (pintype "passive"))
      (node (ref "UC633") (pin "9") (pintype "passive"))
    )
    (net (code "143") (name "Net-(CC66-Pad2)") (class "Default")
      (node (ref "CC66") (pin "2") (pinfunction "2_2") (pintype "passive"))
      (node (ref "RC138") (pin "1") (pinfunction "1_1") (pintype "passive"))
      (node (ref "RC139") (pin "2") (pinfunction "2_2") (pintype "passive"))
    )
    (net (code "144") (name "Net-(CC68-Pad1)") (class "Default")
      (node (ref "CC68") (pin "1") (pinfunction "1_1") (pintype "passive"))
      (node (ref "RC139") (pin "1") (pinfunction "1_1") (pintype "passive"))
      (node (ref "UC633") (pin "10") (pintype "passive"))
    )
    (net (code "145") (name "Net-(CC69-Pad1)") (class "Default")
      (node (ref "CC69") (pin "1") (pinfunction "1_1") (pintype "passive"))
      (node (ref "RC131") (pin "2") (pinfunction "2_2") (pintype "passive"))
      (node (ref "RC140") (pin "2") (pinfunction "2_2") (pintype "passive"))
      (node (ref "UC633") (pin "12") (pintype "passive"))
    )
    (net (code "146") (name "Net-(CC73-Pad2)") (class "Default")
      (node (ref "CC73") (pin "2") (pinfunction "2_2") (pintype "passive"))
      (node (ref "RC149") (pin "2") (pinfunction "2_2") (pintype "passive"))
      (node (ref "UC636") (pin "8") (pintype "passive"))
    )
    (net (code "147") (name "Net-(CC75-Pad2)") (class "Default")
      (node (ref "CC75") (pin "2") (pinfunction "2_2") (pintype "passive"))
      (node (ref "RC135") (pin "2") (pinfunction "2_2") (pintype "passive"))
      (node (ref "RC146") (pin "2") (pinfunction "2_2") (pintype "passive"))
      (node (ref "RC152") (pin "1") (pinfunction "1_1") (pintype "passive"))
      (node (ref "TP17") (pin "1") (pinfunction "1_1") (pintype "passive"))
      (node (ref "UC625") (pin "7") (pintype "passive"))
    )
    (net (code "148") (name "Net-(CC80-Pad1)") (class "Default")
      (node (ref "CC80") (pin "1") (pinfunction "1_1") (pintype "passive"))
      (node (ref "RC130") (pin "1") (pinfunction "1_1") (pintype "passive"))
      (node (ref "RC134") (pin "1") (pinfunction "1_1") (pintype "passive"))
      (node (ref "RC157") (pin "1") (pinfunction "1_1") (pintype "passive"))
      (node (ref "UC636") (pin "7") (pintype "passive"))
      (node (ref "UC636") (pin "9") (pintype "passive"))
    )
    (net (code "149") (name "Net-(CC85-Pad2)") (class "Default")
      (node (ref "CC85") (pin "2") (pinfunction "2_2") (pintype "passive"))
      (node (ref "RC165") (pin "2") (pinfunction "2_2") (pintype "passive"))
      (node (ref "RC167") (pin "2") (pinfunction "2_2") (pintype "passive"))
      (node (ref "UC627") (pin "12") (pintype "passive"))
    )
    (net (code "150") (name "Net-(CC86-Pad2)") (class "Default")
      (node (ref "CC86") (pin "2") (pinfunction "2_2") (pintype "passive"))
      (node (ref "RC163") (pin "2") (pinfunction "2_2") (pintype "passive"))
      (node (ref "UC637") (pin "10") (pintype "passive"))
    )
    (net (code "151") (name "Net-(CC91-Pad1)") (class "Default")
      (node (ref "CC91") (pin "1") (pinfunction "1_1") (pintype "passive"))
      (node (ref "RC177") (pin "2") (pinfunction "2_2") (pintype "passive"))
      (node (ref "RC178") (pin "2") (pinfunction "2_2") (pintype "passive"))
      (node (ref "UC627") (pin "13") (pintype "passive"))
    )
    (net (code "152") (name "Net-(CC91-Pad2)") (class "Default")
      (node (ref "CC91") (pin "2") (pinfunction "2_2") (pintype "passive"))
      (node (ref "RC169") (pin "2") (pinfunction "2_2") (pintype "passive"))
      (node (ref "RC178") (pin "1") (pinfunction "1_1") (pintype "passive"))
      (node (ref "UC627") (pin "14") (pintype "passive"))
    )
    (net (code "153") (name "Net-(CC92-Pad2)") (class "Default")
      (node (ref "CC92") (pin "2") (pinfunction "2_2") (pintype "passive"))
      (node (ref "RC174") (pin "2") (pinfunction "2_2") (pintype "passive"))
      (node (ref "UC637") (pin "12") (pintype "passive"))
    )
    (net (code "154") (name "Net-(CC93-Pad2)") (class "Default")
      (node (ref "CC93") (pin "2") (pinfunction "2_2") (pintype "passive"))
      (node (ref "RC172") (pin "1") (pinfunction "1_1") (pintype "passive"))
      (node (ref "UC14") (pin "10") (pinfunction "10_10") (pintype "passive"))
    )
    (net (code "155") (name "Net-(CC94-Pad2)") (class "Default")
      (node (ref "CC94") (pin "2") (pinfunction "2_2") (pintype "passive"))
      (node (ref "RC176") (pin "1") (pinfunction "1_1") (pintype "passive"))
      (node (ref "UC14") (pin "9") (pinfunction "9_9") (pintype "passive"))
    )
    (net (code "156") (name "Net-(CC96-Pad2)") (class "Default")
      (node (ref "CC96") (pin "2") (pinfunction "2_2") (pintype "passive"))
      (node (ref "RC179") (pin "2") (pinfunction "2_2") (pintype "passive"))
      (node (ref "RC180") (pin "2") (pinfunction "2_2") (pintype "passive"))
      (node (ref "UC629") (pin "12") (pintype "passive"))
    )
    (net (code "157") (name "Net-(CC97-Pad1)") (class "Default")
      (node (ref "CC97") (pin "1") (pinfunction "1_1") (pintype "passive"))
      (node (ref "RC191") (pin "2") (pinfunction "2_2") (pintype "passive"))
      (node (ref "RC192") (pin "2") (pinfunction "2_2") (pintype "passive"))
      (node (ref "UC629") (pin "13") (pintype "passive"))
    )
    (net (code "158") (name "Net-(CC97-Pad2)") (class "Default")
      (node (ref "CC97") (pin "2") (pinfunction "2_2") (pintype "passive"))
      (node (ref "RC184") (pin "2") (pinfunction "2_2") (pintype "passive"))
      (node (ref "RC192") (pin "1") (pinfunction "1_1") (pintype "passive"))
      (node (ref "UC629") (pin "14") (pintype "passive"))
    )
    (net (code "159") (name "Net-(CC98-Pad2)") (class "Default")
      (node (ref "CC98") (pin "2") (pinfunction "2_2") (pintype "passive"))
      (node (ref "RC188") (pin "2") (pinfunction "2_2") (pintype "passive"))
      (node (ref "RC593") (pin "2") (pinfunction "2_2") (pintype "passive"))
      (node (ref "UC634") (pin "5") (pintype "passive"))
    )
    (net (code "160") (name "Net-(CC99-Pad2)") (class "Default")
      (node (ref "CC99") (pin "2") (pinfunction "2_2") (pintype "passive"))
      (node (ref "RC196") (pin "1") (pinfunction "1_1") (pintype "passive"))
      (node (ref "UC16") (pin "10") (pinfunction "10_10") (pintype "passive"))
    )
    (net (code "161") (name "Net-(CC100-Pad2)") (class "Default")
      (node (ref "CC100") (pin "2") (pinfunction "2_2") (pintype "passive"))
      (node (ref "RC197") (pin "1") (pinfunction "1_1") (pintype "passive"))
      (node (ref "UC16") (pin "9") (pinfunction "9_9") (pintype "passive"))
    )
    (net (code "162") (name "Net-(CC101-Pad2)") (class "Default")
      (node (ref "CC101") (pin "2") (pinfunction "2_2") (pintype "passive"))
      (node (ref "RC198") (pin "2") (pinfunction "2_2") (pintype "passive"))
      (node (ref "RC199") (pin "2") (pinfunction "2_2") (pintype "passive"))
      (node (ref "UC630") (pin "12") (pintype "passive"))
    )
    (net (code "163") (name "Net-(CC102-Pad1)") (class "Default")
      (node (ref "CC102") (pin "1") (pinfunction "1_1") (pintype "passive"))
      (node (ref "RC202") (pin "2") (pinfunction "2_2") (pintype "passive"))
      (node (ref "RC203") (pin "2") (pinfunction "2_2") (pintype "passive"))
      (node (ref "UC630") (pin "13") (pintype "passive"))
    )
    (net (code "164") (name "Net-(CC102-Pad2)") (class "Default")
      (node (ref "CC102") (pin "2") (pinfunction "2_2") (pintype "passive"))
      (node (ref "RC201") (pin "2") (pinfunction "2_2") (pintype "passive"))
      (node (ref "RC203") (pin "1") (pinfunction "1_1") (pintype "passive"))
      (node (ref "UC630") (pin "14") (pintype "passive"))
    )
    (net (code "165") (name "Net-(CC446-Pad2)") (class "Default")
      (node (ref "CC446") (pin "2") (pinfunction "2_2") (pintype "passive"))
      (node (ref "RC707") (pin "1") (pinfunction "1_1") (pintype "passive"))
      (node (ref "RC708") (pin "2") (pinfunction "2_2") (pintype "passive"))
    )
    (net (code "166") (name "Net-(CC447-Pad1)") (class "Default")
      (node (ref "CC447") (pin "1") (pinfunction "1_1") (pintype "passive"))
      (node (ref "RC708") (pin "1") (pinfunction "1_1") (pintype "passive"))
      (node (ref "UC634") (pin "3") (pintype "passive"))
    )
    (net (code "167") (name "Net-(CC448-Pad2)") (class "Default")
      (node (ref "CC448") (pin "2") (pinfunction "2_2") (pintype "passive"))
      (node (ref "RC709") (pin "1") (pinfunction "1_1") (pintype "passive"))
      (node (ref "RC710") (pin "2") (pinfunction "2_2") (pintype "passive"))
    )
    (net (code "168") (name "Net-(CC449-Pad1)") (class "Default")
      (node (ref "CC449") (pin "1") (pinfunction "1_1") (pintype "passive"))
      (node (ref "RC710") (pin "1") (pinfunction "1_1") (pintype "passive"))
      (node (ref "UC634") (pin "12") (pintype "passive"))
    )
    (net (code "169") (name "Net-(DC9-Pad1)") (class "Default")
      (node (ref "DC9") (pin "1") (pinfunction "1_1") (pintype "passive"))
      (node (ref "RC125") (pin "1") (pinfunction "1_1") (pintype "passive"))
    )
    (net (code "170") (name "Net-(DC10-Pad1)") (class "Default")
      (node (ref "DC10") (pin "1") (pinfunction "1_1") (pintype "passive"))
      (node (ref "RC134") (pin "2") (pinfunction "2_2") (pintype "passive"))
    )
    (net (code "171") (name "Net-(RC3-Pad1)") (class "Default")
      (node (ref "RC3") (pin "1") (pinfunction "1_1") (pintype "passive"))
      (node (ref "UC627") (pin "6") (pintype "passive"))
      (node (ref "UC627") (pin "7") (pintype "passive"))
    )
    (net (code "172") (name "Net-(RC7-Pad2)") (class "Default")
      (node (ref "RC7") (pin "2") (pinfunction "2_2") (pintype "passive"))
      (node (ref "RC8") (pin "1") (pinfunction "1_1") (pintype "passive"))
      (node (ref "UC627") (pin "10") (pintype "passive"))
      (node (ref "UC627") (pin "5") (pintype "passive"))
    )
    (net (code "173") (name "Net-(RC14-Pad1)") (class "Default")
      (node (ref "RC14") (pin "1") (pinfunction "1_1") (pintype "passive"))
      (node (ref "UC627") (pin "8") (pintype "passive"))
      (node (ref "UC627") (pin "9") (pintype "passive"))
    )
    (net (code "174") (name "Net-(RC43-Pad2)") (class "Default")
      (node (ref "RC43") (pin "2") (pinfunction "2_2") (pintype "passive"))
      (node (ref "UC50") (pin "11") (pintype "output"))
    )
    (net (code "175") (name "Net-(RC65-Pad1)") (class "Default")
      (node (ref "RC65") (pin "1") (pinfunction "1_1") (pintype "passive"))
      (node (ref "UC629") (pin "8") (pintype "passive"))
      (node (ref "UC629") (pin "9") (pintype "passive"))
    )
    (net (code "176") (name "Net-(RC68-Pad2)") (class "Default")
      (node (ref "RC68") (pin "2") (pinfunction "2_2") (pintype "passive"))
      (node (ref "RC70") (pin "1") (pinfunction "1_1") (pintype "passive"))
      (node (ref "UC629") (pin "10") (pintype "passive"))
      (node (ref "UC629") (pin "5") (pintype "passive"))
    )
    (net (code "177") (name "Net-(RC72-Pad1)") (class "Default")
      (node (ref "RC72") (pin "1") (pinfunction "1_1") (pintype "passive"))
      (node (ref "UC629") (pin "6") (pintype "passive"))
      (node (ref "UC629") (pin "7") (pintype "passive"))
    )
    (net (code "178") (name "Net-(RC111-Pad1)") (class "Default")
      (node (ref "RC111") (pin "1") (pinfunction "1_1") (pintype "passive"))
      (node (ref "UC630") (pin "6") (pintype "passive"))
      (node (ref "UC630") (pin "7") (pintype "passive"))
    )
    (net (code "179") (name "Net-(RC114-Pad1)") (class "Default")
      (node (ref "RC114") (pin "1") (pinfunction "1_1") (pintype "passive"))
      (node (ref "UC637") (pin "3") (pintype "passive"))
    )
    (net (code "180") (name "Net-(RC117-Pad2)") (class "Default")
      (node (ref "RC117") (pin "2") (pinfunction "2_2") (pintype "passive"))
      (node (ref "RC122") (pin "1") (pinfunction "1_1") (pintype "passive"))
      (node (ref "UC630") (pin "10") (pintype "passive"))
      (node (ref "UC630") (pin "5") (pintype "passive"))
    )
    (net (code "181") (name "Net-(RC119-Pad1)") (class "Default")
      (node (ref "RC119") (pin "1") (pinfunction "1_1") (pintype "passive"))
      (node (ref "UC637") (pin "1") (pintype "passive"))
      (node (ref "UC637") (pin "2") (pintype "passive"))
    )
    (net (code "182") (name "Net-(RC128-Pad1)") (class "Default")
      (node (ref "RC128") (pin "1") (pinfunction "1_1") (pintype "passive"))
      (node (ref "UC630") (pin "8") (pintype "passive"))
      (node (ref "UC630") (pin "9") (pintype "passive"))
    )
    (net (code "183") (name "Net-(RC129-Pad1)") (class "Default")
      (node (ref "RC129") (pin "1") (pinfunction "1_1") (pintype "passive"))
      (node (ref "RC130") (pin "2") (pinfunction "2_2") (pintype "passive"))
      (node (ref "RC511") (pin "1") (pinfunction "1_1") (pintype "passive"))
    )
    (net (code "184") (name "Net-(RC143-Pad1)") (class "Default")
      (node (ref "RC143") (pin "1") (pinfunction "1_1") (pintype "passive"))
      (node (ref "RC149") (pin "1") (pinfunction "1_1") (pintype "passive"))
      (node (ref "UC637") (pin "7") (pintype "passive"))
    )
    (net (code "185") (name "Net-(RC143-Pad2)") (class "Default")
      (node (ref "RC143") (pin "2") (pinfunction "2_2") (pintype "passive"))
      (node (ref "RC147") (pin "1") (pinfunction "1_1") (pintype "passive"))
      (node (ref "UC637") (pin "6") (pintype "passive"))
    )
    (net (code "186") (name "Net-(RC150-Pad2)") (class "Default")
      (node (ref "RC150") (pin "2") (pinfunction "2_2") (pintype "passive"))
      (node (ref "UC637") (pin "5") (pintype "passive"))
    )
    (net (code "187") (name "Net-(RC161-Pad1)") (class "Default")
      (node (ref "RC161") (pin "1") (pinfunction "1_1") (pintype "passive"))
      (node (ref "UC636") (pin "13") (pintype "passive"))
    )
    (net (code "188") (name "Net-(RC162-4)") (class "Default")
      (node (ref "RC162") (pin "8") (pinfunction "4_8") (pintype "passive"))
      (node (ref "UC14") (pin "4") (pinfunction "4_4") (pintype "passive"))
    )
    (net (code "189") (name "Net-(RC162-5)") (class "Default")
      (node (ref "RC162") (pin "7") (pinfunction "5_7") (pintype "passive"))
      (node (ref "UC14") (pin "3") (pinfunction "3_3") (pintype "passive"))
    )
    (net (code "190") (name "Net-(RC162-7)") (class "Default")
      (node (ref "RC162") (pin "5") (pinfunction "7_5") (pintype "passive"))
      (node (ref "UC14") (pin "1") (pinfunction "1_1") (pintype "passive"))
    )
    (net (code "191") (name "Net-(RC162-Pad6)") (class "Default")
      (node (ref "RC162") (pin "6") (pinfunction "6_6") (pintype "passive"))
      (node (ref "UC14") (pin "2") (pinfunction "2_2") (pintype "passive"))
    )
    (net (code "192") (name "Net-(RC164-Pad1)") (class "Default")
      (node (ref "RC164") (pin "1") (pinfunction "1_1") (pintype "passive"))
      (node (ref "UC638") (pin "3") (pintype "passive"))
    )
    (net (code "193") (name "Net-(RC164-Pad2)") (class "Default")
      (node (ref "RC164") (pin "2") (pinfunction "2_2") (pintype "passive"))
      (node (ref "UC14") (pin "13") (pinfunction "13_13") (pintype "passive"))
    )
    (net (code "194") (name "Net-(RC166-Pad1)") (class "Default")
      (node (ref "RC166") (pin "1") (pinfunction "1_1") (pintype "passive"))
      (node (ref "UC638") (pin "1") (pintype "passive"))
      (node (ref "UC638") (pin "2") (pintype "passive"))
    )
    (net (code "195") (name "Net-(RC170-Pad2)") (class "Default")
      (node (ref "RC170") (pin "2") (pinfunction "2_2") (pintype "passive"))
      (node (ref "UC14") (pin "11") (pinfunction "11_11") (pintype "passive"))
    )
    (net (code "196") (name "Net-(RC171-Pad1)") (class "Default")
      (node (ref "RC171") (pin "1") (pinfunction "1_1") (pintype "passive"))
      (node (ref "UC637") (pin "8") (pintype "passive"))
      (node (ref "UC637") (pin "9") (pintype "passive"))
    )
    (net (code "197") (name "Net-(RC173-Pad1)") (class "Default")
      (node (ref "RC173") (pin "1") (pinfunction "1_1") (pintype "passive"))
      (node (ref "UC14") (pin "5") (pinfunction "5_5") (pintype "passive"))
    )
    (net (code "198") (name "Net-(RC175-Pad1)") (class "Default")
      (node (ref "RC175") (pin "1") (pinfunction "1_1") (pintype "passive"))
      (node (ref "UC637") (pin "13") (pintype "passive"))
      (node (ref "UC637") (pin "14") (pintype "passive"))
    )
    (net (code "199") (name "Net-(RC182-Pad1)") (class "Default")
      (node (ref "RC182") (pin "1") (pinfunction "1_1") (pintype "passive"))
      (node (ref "RC185") (pin "1") (pinfunction "1_1") (pintype "passive"))
    )
    (net (code "200") (name "Net-(RC182-Pad2)") (class "Default")
      (node (ref "RC182") (pin "2") (pinfunction "2_2") (pintype "passive"))
      (node (ref "RC593") (pin "1") (pinfunction "1_1") (pintype "passive"))
    )
    (net (code "201") (name "Net-(RC183-Pad1)") (class "Default")
      (node (ref "RC183") (pin "1") (pinfunction "1_1") (pintype "passive"))
      (node (ref "UC634") (pin "6") (pintype "passive"))
      (node (ref "UC634") (pin "7") (pintype "passive"))
    )
    (net (code "202") (name "Net-(RC185-Pad2)") (class "Default")
      (node (ref "RC185") (pin "2") (pinfunction "2_2") (pintype "passive"))
      (node (ref "RC195") (pin "1") (pinfunction "1_1") (pintype "passive"))
    )
    (net (code "203") (name "Net-(RC186-Pad1)") (class "Default")
      (node (ref "RC186") (pin "1") (pinfunction "1_1") (pintype "passive"))
      (node (ref "UC638") (pin "5") (pintype "passive"))
    )
    (net (code "204") (name "Net-(RC186-Pad2)") (class "Default")
      (node (ref "RC186") (pin "2") (pinfunction "2_2") (pintype "passive"))
      (node (ref "UC16") (pin "3") (pinfunction "3_3") (pintype "passive"))
    )
    (net (code "205") (name "Net-(RC187-Pad2)") (class "Default")
      (node (ref "RC187") (pin "2") (pinfunction "2_2") (pintype "passive"))
      (node (ref "UC638") (pin "8") (pintype "passive"))
      (node (ref "UC638") (pin "9") (pintype "passive"))
    )
    (net (code "206") (name "Net-(RC189-Pad1)") (class "Default")
      (node (ref "RC189") (pin "1") (pinfunction "1_1") (pintype "passive"))
      (node (ref "UC638") (pin "6") (pintype "passive"))
      (node (ref "UC638") (pin "7") (pintype "passive"))
    )
    (net (code "207") (name "Net-(RC190-Pad1)") (class "Default")
      (node (ref "RC190") (pin "1") (pinfunction "1_1") (pintype "passive"))
      (node (ref "UC16") (pin "13") (pinfunction "13_13") (pintype "passive"))
    )
    (net (code "208") (name "Net-(RC190-Pad2)") (class "Default")
      (node (ref "RC190") (pin "2") (pinfunction "2_2") (pintype "passive"))
      (node (ref "UC638") (pin "10") (pintype "passive"))
    )
    (net (code "209") (name "Net-(RC193-Pad1)") (class "Default")
      (node (ref "RC193") (pin "1") (pinfunction "1_1") (pintype "passive"))
      (node (ref "UC16") (pin "11") (pinfunction "11_11") (pintype "passive"))
    )
    (net (code "210") (name "Net-(RC194-Pad1)") (class "Default")
      (node (ref "RC194") (pin "1") (pinfunction "1_1") (pintype "passive"))
      (node (ref "UC16") (pin "4") (pinfunction "4_4") (pintype "passive"))
    )
    (net (code "211") (name "Net-(RC506-Pad2)") (class "Default")
      (node (ref "RC506") (pin "2") (pinfunction "2_2") (pintype "passive"))
      (node (ref "RC709") (pin "2") (pinfunction "2_2") (pintype "passive"))
      (node (ref "RC79") (pin "1") (pinfunction "1_1") (pintype "passive"))
    )
    (net (code "212") (name "Net-(RC507-Pad2)") (class "Default")
      (node (ref "RC507") (pin "2") (pinfunction "2_2") (pintype "passive"))
      (node (ref "RC60") (pin "1") (pinfunction "1_1") (pintype "passive"))
      (node (ref "RC707") (pin "2") (pinfunction "2_2") (pintype "passive"))
    )
    (net (code "213") (name "Net-(RC533-Pad2)") (class "Default")
      (node (ref "RC533") (pin "2") (pinfunction "2_2") (pintype "passive"))
      (node (ref "UC50") (pin "1") (pintype "input"))
      (node (ref "UC50") (pin "6") (pintype "output"))
    )
    (net (code "214") (name "Net-(RC706-Pad1)") (class "Default")
      (node (ref "RC706") (pin "1") (pinfunction "1_1") (pintype "passive"))
      (node (ref "UC636") (pin "2") (pintype "passive"))
    )
    (net (code "215") (name "Net-(UC625A-+)") (class "Default")
      (node (ref "CC49") (pin "2") (pinfunction "2_2") (pintype "passive"))
      (node (ref "RC103") (pin "1") (pinfunction "1_1") (pintype "passive"))
      (node (ref "RC104") (pin "2") (pinfunction "2_2") (pintype "passive"))
      (node (ref "UC625") (pin "3") (pinfunction "+_3") (pintype "passive"))
    )
    (net (code "216") (name "Net-(UC625A--)") (class "Default")
      (node (ref "CC60") (pin "1") (pinfunction "1_1") (pintype "passive"))
      (node (ref "RC118") (pin "2") (pinfunction "2_2") (pintype "passive"))
      (node (ref "RC126") (pin "2") (pinfunction "2_2") (pintype "passive"))
      (node (ref "UC625") (pin "2") (pinfunction "-_2") (pintype "passive"))
    )
    (net (code "217") (name "Net-(UC625B-+)") (class "Default")
      (node (ref "CC67") (pin "2") (pinfunction "2_2") (pintype "passive"))
      (node (ref "RC142") (pin "1") (pinfunction "1_1") (pintype "passive"))
      (node (ref "RC145") (pin "2") (pinfunction "2_2") (pintype "passive"))
      (node (ref "UC625") (pin "5") (pinfunction "+_5") (pintype "passive"))
    )
    (net (code "218") (name "Net-(UC625B--)") (class "Default")
      (node (ref "CC75") (pin "1") (pinfunction "1_1") (pintype "passive"))
      (node (ref "RC151") (pin "2") (pinfunction "2_2") (pintype "passive"))
      (node (ref "RC152") (pin "2") (pinfunction "2_2") (pintype "passive"))
      (node (ref "UC625") (pin "6") (pinfunction "-_6") (pintype "passive"))
    )
    (net (code "219") (name "Net-(UC626B-2)") (class "Default")
      (node (ref "CC70") (pin "1") (pinfunction "1_1") (pintype "passive"))
      (node (ref "RC135") (pin "1") (pinfunction "1_1") (pintype "passive"))
      (node (ref "UC626") (pin "6") (pinfunction "2_6") (pintype "passive"))
    )
    (net (code "220") (name "Net-(UC626B-3)") (class "Default")
      (node (ref "CC65") (pin "2") (pinfunction "2_2") (pintype "passive"))
      (node (ref "RC115") (pin "1") (pinfunction "1_1") (pintype "passive"))
      (node (ref "RC124") (pin "1") (pinfunction "1_1") (pintype "passive"))
      (node (ref "RC125") (pin "2") (pinfunction "2_2") (pintype "passive"))
      (node (ref "UC626") (pin "3") (pinfunction "3_3") (pintype "passive"))
      (node (ref "UC626") (pin "5") (pinfunction "3_5") (pintype "passive"))
    )
    (net (code "221") (name "Net-(UC634-Pad8)") (class "Default")
      (node (ref "UC634") (pin "8") (pintype "passive"))
      (node (ref "UC634") (pin "9") (pintype "passive"))
    )
    (net (code "222") (name "REF3V") (class "Default")
      (node (ref "RC117") (pin "1") (pinfunction "1_1") (pintype "passive"))
      (node (ref "RC168") (pin "1") (pinfunction "1_1") (pintype "passive"))
      (node (ref "RC181") (pin "1") (pinfunction "1_1") (pintype "passive"))
      (node (ref "RC200") (pin "1") (pinfunction "1_1") (pintype "passive"))
      (node (ref "RC506") (pin "1") (pinfunction "1_1") (pintype "passive"))
      (node (ref "RC507") (pin "1") (pinfunction "1_1") (pintype "passive"))
      (node (ref "RC68") (pin "1") (pinfunction "1_1") (pintype "passive"))
      (node (ref "RC7") (pin "1") (pinfunction "1_1") (pintype "passive"))
    )
    (net (code "223") (name "V33D") (class "Default")
      (node (ref "CC46") (pin "1") (pinfunction "1_1") (pintype "passive"))
      (node (ref "RC110") (pin "1") (pinfunction "1_1") (pintype "passive"))
      (node (ref "RC532") (pin "1") (pinfunction "1_1") (pintype "passive"))
      (node (ref "UC50") (pin "14") (pinfunction "VCC_14") (pintype "passive"))
    )
    (net (code "224") (name "Vpv1+") (class "Default")
      (node (ref "RC2") (pin "2") (pinfunction "2_2") (pintype "passive"))
    )
    (net (code "225") (name "Vpv1-") (class "Default")
      (node (ref "RC15") (pin "2") (pinfunction "2_2") (pintype "passive"))
    )
    (net (code "226") (name "Vpv2+") (class "Default")
      (node (ref "RC32") (pin "2") (pinfunction "2_2") (pintype "passive"))
    )
    (net (code "227") (name "Vpv2-") (class "Default")
      (node (ref "RC46") (pin "2") (pinfunction "2_2") (pintype "passive"))
    )
    (net (code "228") (name "unconnected-(UC626-Pad4)") (class "Default")
      (node (ref "UC626") (pin "4") (pinfunction "4_4") (pintype "power_in"))
    )
    (net (code "229") (name "unconnected-(UC626-Pad8)") (class "Default")
      (node (ref "UC626") (pin "8") (pinfunction "8_8") (pintype "power_in"))
    )
  )
)
